# Intercom.net
KiCad netlist of a schematic drawn in EAGLE
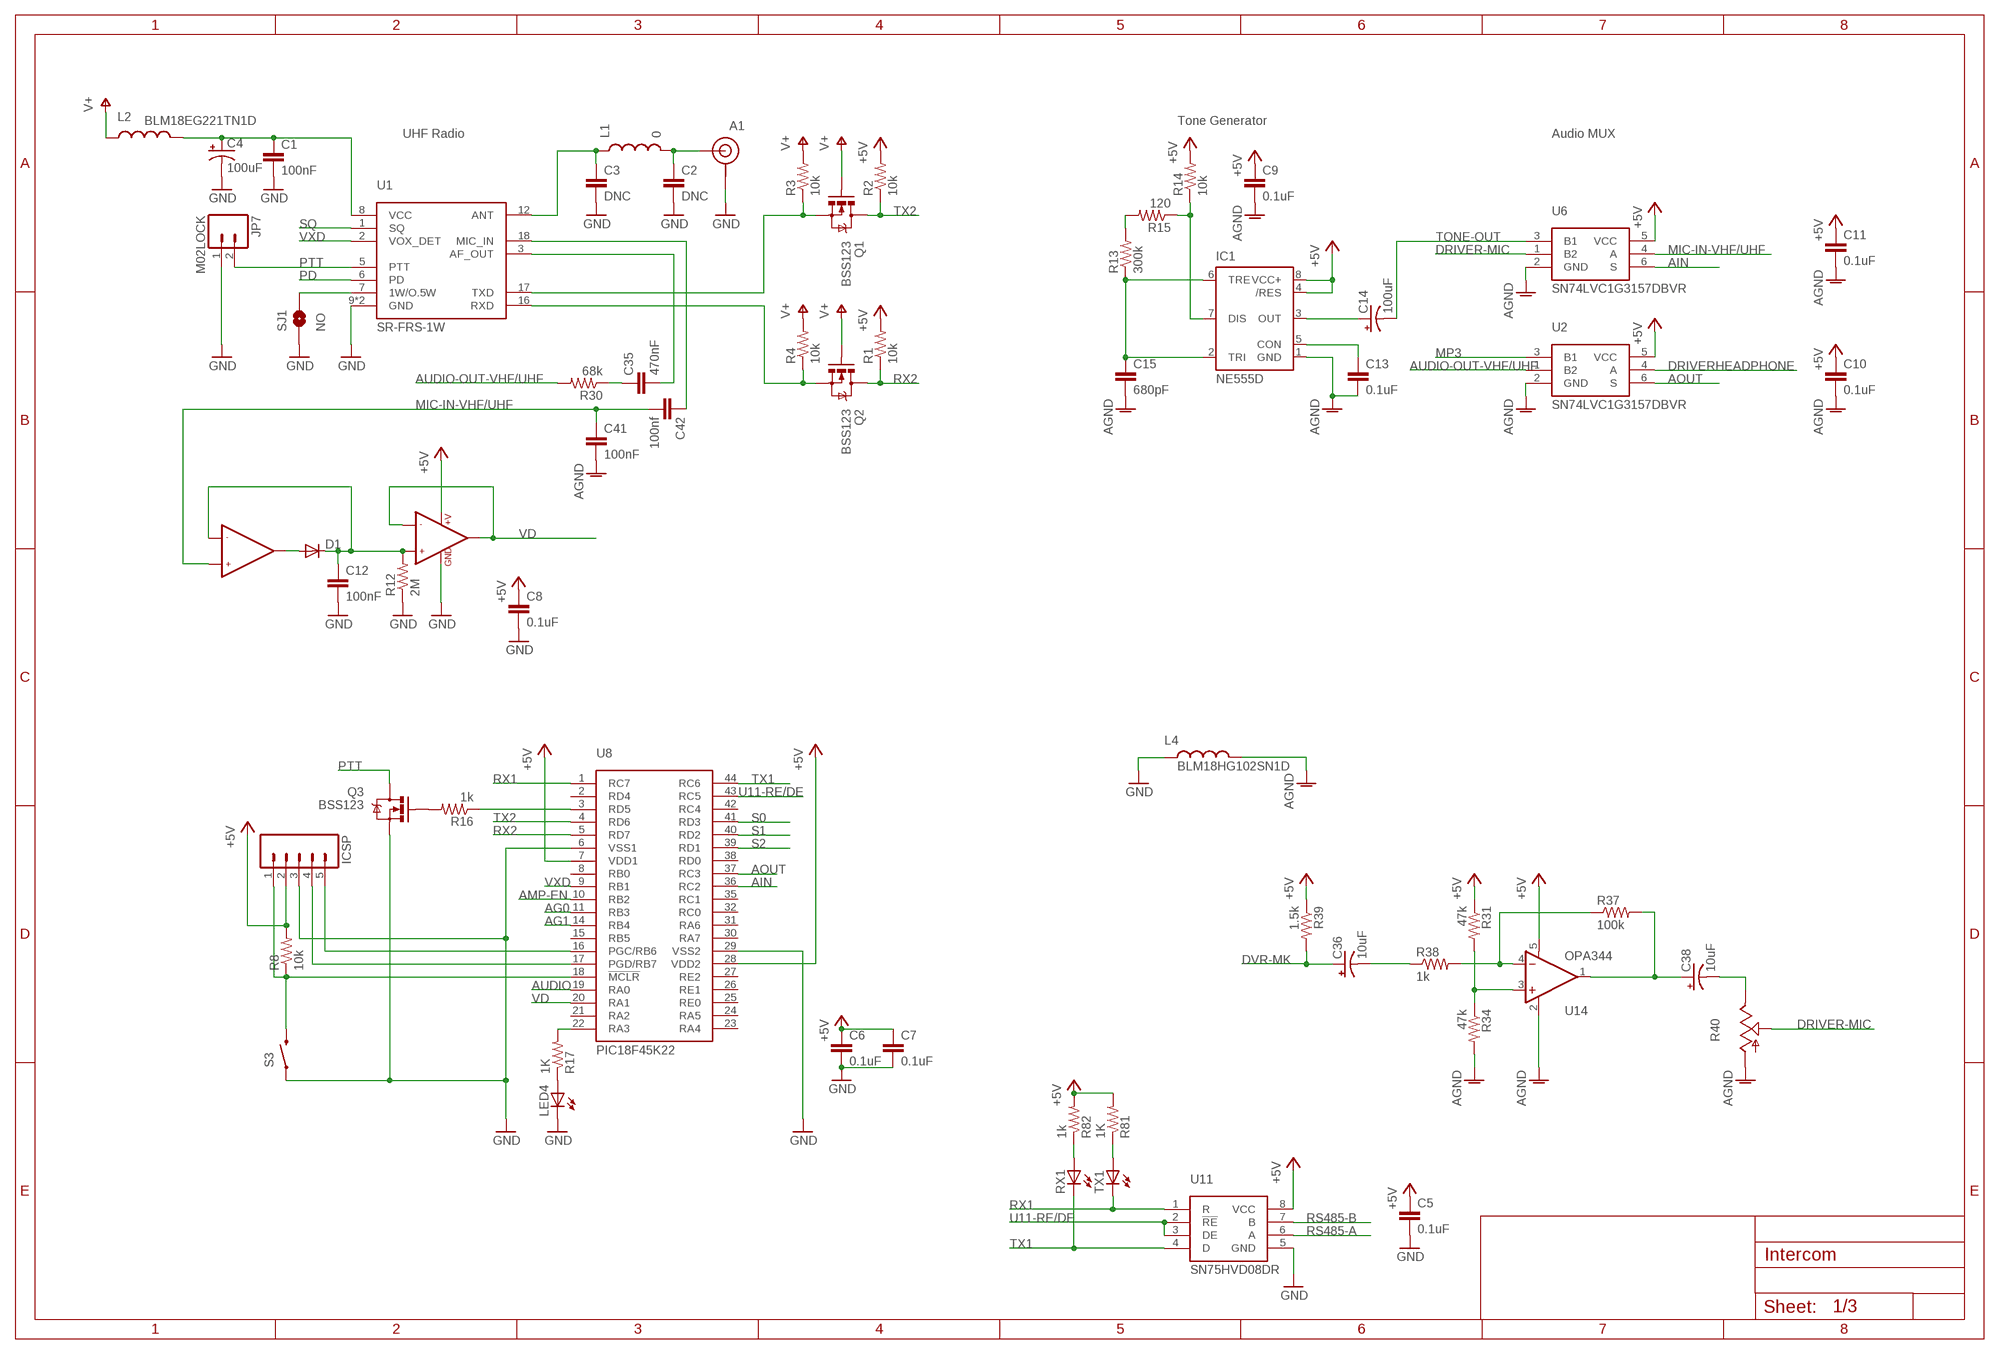
[diagram p0: schematic, sheet 1]
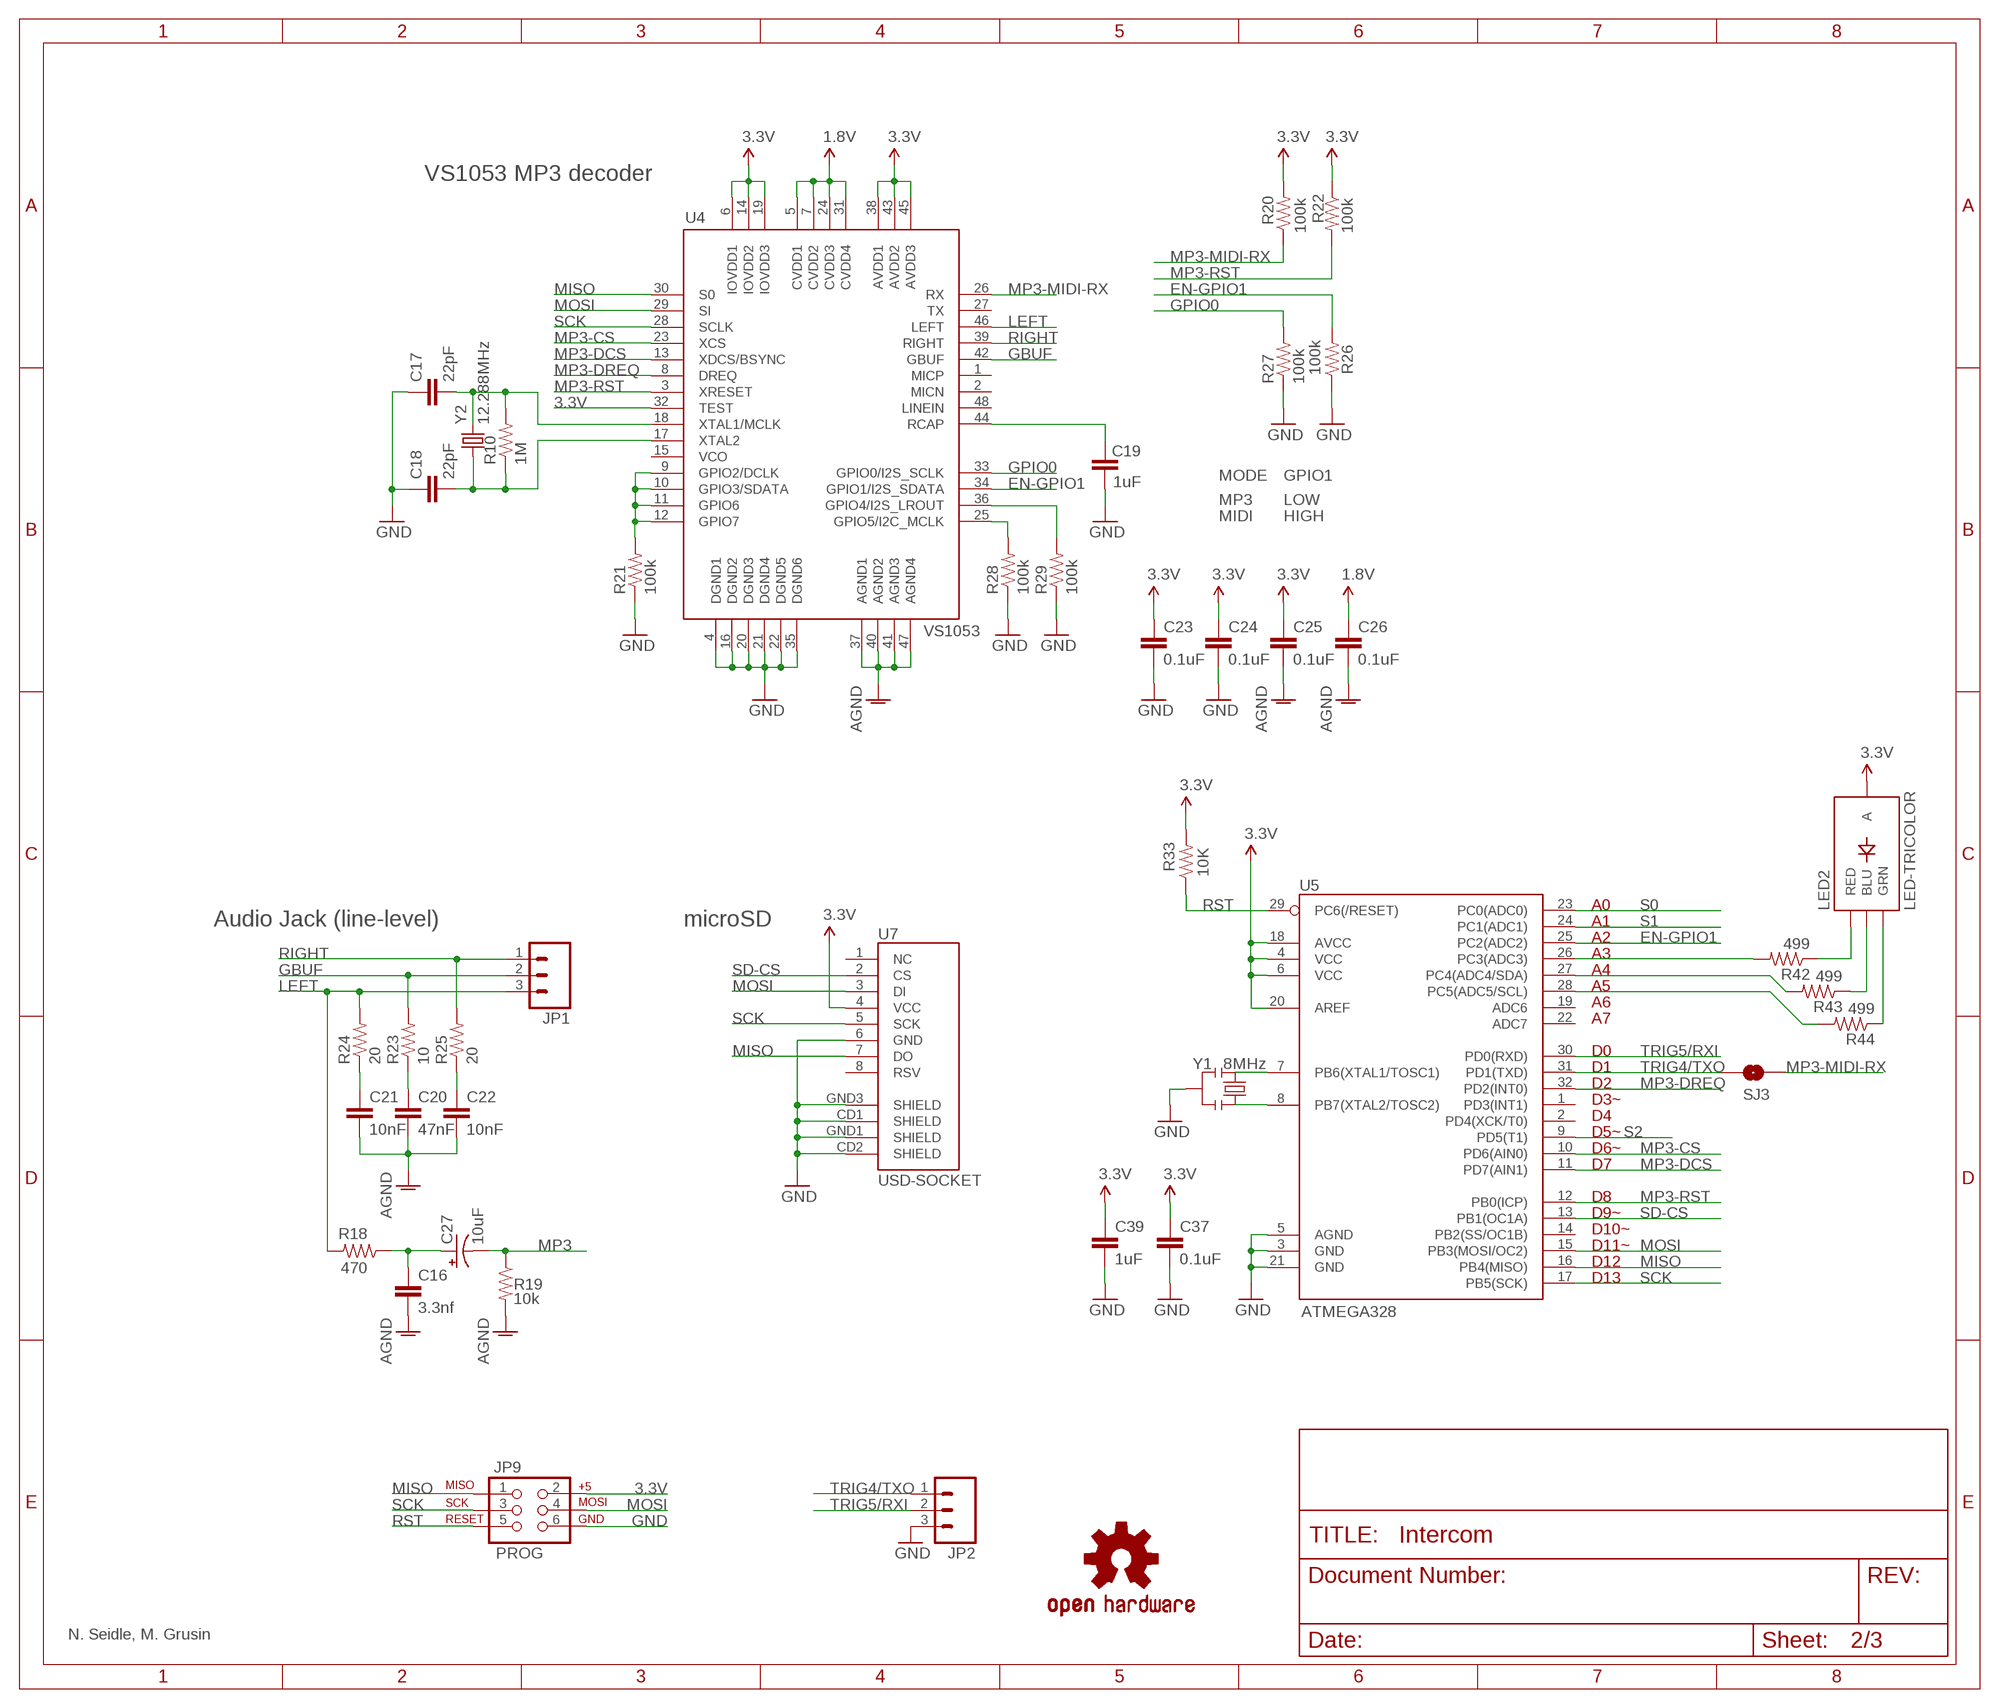
[diagram p1: schematic, sheet 2]
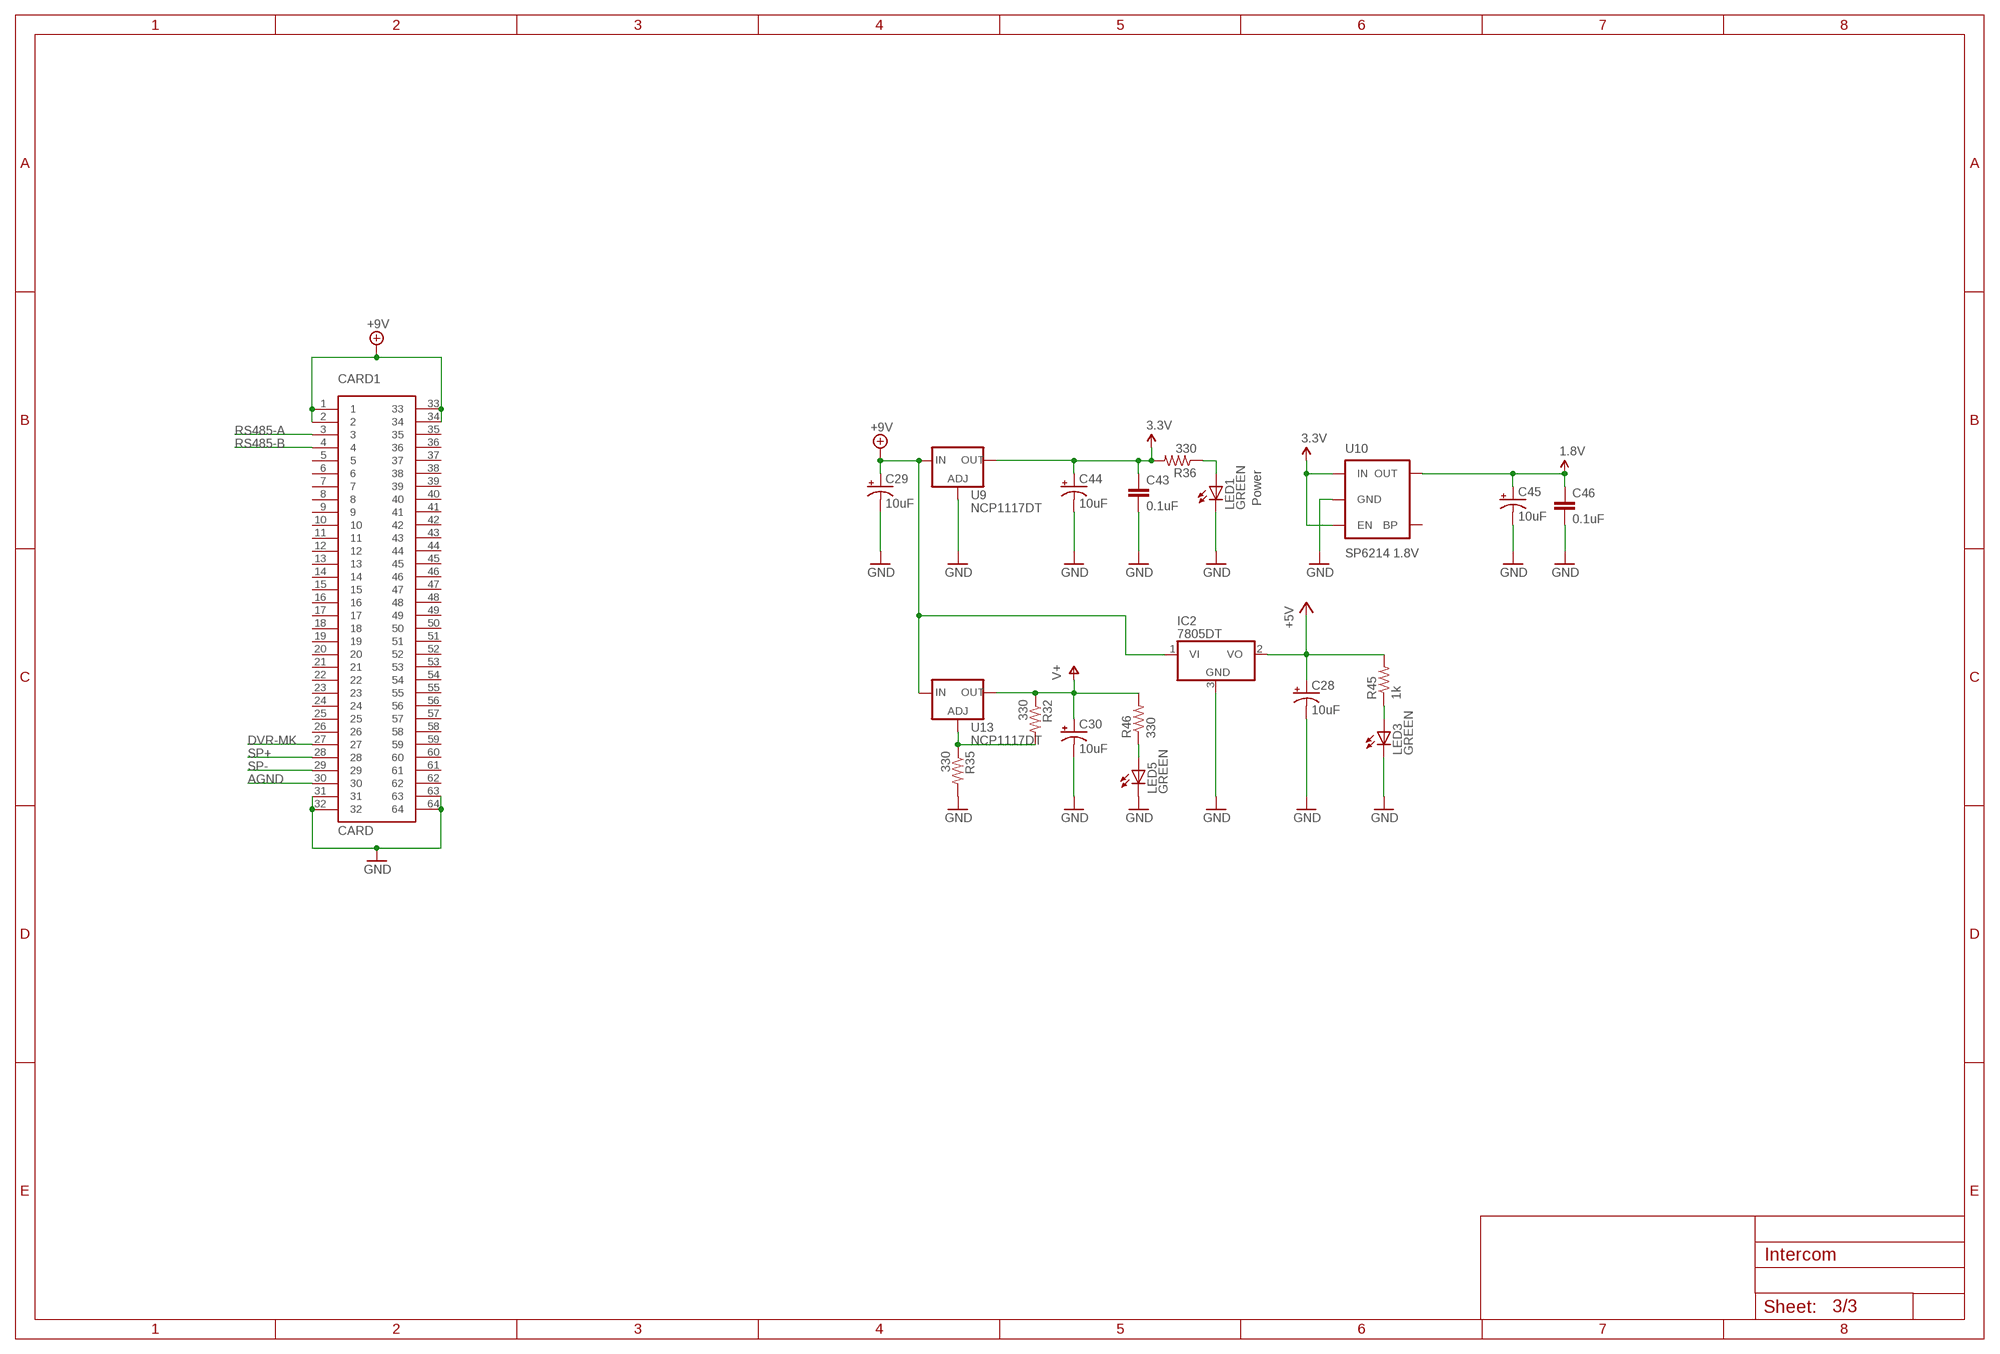
[diagram p2: schematic, sheet 3]

(export (version "E")
  (design (tool "Eeschema 10.0.6"))
  (components
    (comp (ref "C16")
      (value "3.3nf")
      (footprint "eagle-import:0805")
      (libsource (lib "eagle-import") (part "CAP0805"))
    )
    (comp (ref "C17")
      (value "22pF")
      (footprint "eagle-import:0805")
      (libsource (lib "eagle-import") (part "CAP0805"))
    )
    (comp (ref "C18")
      (value "22pF")
      (footprint "eagle-import:0805")
      (libsource (lib "eagle-import") (part "CAP0805"))
    )
    (comp (ref "C19")
      (value "1uF")
      (footprint "eagle-import:0805")
      (libsource (lib "eagle-import") (part "CAP0805"))
    )
    (comp (ref "C20")
      (value "47nF")
      (footprint "eagle-import:0805")
      (libsource (lib "eagle-import") (part "CAP0805"))
    )
    (comp (ref "C21")
      (value "10nF")
      (footprint "eagle-import:0805")
      (libsource (lib "eagle-import") (part "CAP0805"))
    )
    (comp (ref "C22")
      (value "10nF")
      (footprint "eagle-import:0805")
      (libsource (lib "eagle-import") (part "CAP0805"))
    )
    (comp (ref "C23")
      (value "0.1uF")
      (footprint "eagle-import:0805")
      (libsource (lib "eagle-import") (part "CAP0805"))
    )
    (comp (ref "C24")
      (value "0.1uF")
      (footprint "eagle-import:0805")
      (libsource (lib "eagle-import") (part "CAP0805"))
    )
    (comp (ref "C25")
      (value "0.1uF")
      (footprint "eagle-import:0805")
      (libsource (lib "eagle-import") (part "CAP0805"))
    )
    (comp (ref "C26")
      (value "0.1uF")
      (footprint "eagle-import:0805")
      (libsource (lib "eagle-import") (part "CAP0805"))
    )
    (comp (ref "C27")
      (value "10uF")
      (footprint "eagle-import:CT6032")
      (libsource (lib "eagle-import") (part "CPOL-USCT6032"))
    )
    (comp (ref "C37")
      (value "0.1uF")
      (footprint "eagle-import:0805")
      (libsource (lib "eagle-import") (part "CAP0805"))
    )
    (comp (ref "C39")
      (value "1uF")
      (footprint "eagle-import:0805")
      (libsource (lib "eagle-import") (part "CAP0805"))
    )
    (comp (ref "JP1")
      (value "M03PTH")
      (footprint "eagle-import:1X03")
      (libsource (lib "eagle-import") (part "M03PTH"))
    )
    (comp (ref "JP2")
      (value "M03LOCK_LONGPADS")
      (footprint "eagle-import:1X03_LOCK_LONGPADS")
      (libsource (lib "eagle-import") (part "M03LOCK_LONGPADS"))
    )
    (comp (ref "JP9")
      (value "PROG")
      (footprint "eagle-import:2X3-NS")
      (libsource (lib "eagle-import") (part "AVR_SPI_PRG_6NS"))
    )
    (comp (ref "LED2")
      (value "LED-TRICOLOR")
      (footprint "eagle-import:LED-TRICOLOR-SMD")
      (libsource (lib "eagle-import") (part "LED-TRICOLOR"))
    )
    (comp (ref "R10")
      (value "1M")
      (footprint "eagle-import:0805")
      (libsource (lib "eagle-import") (part "RESISTOR0805-RES"))
    )
    (comp (ref "R18")
      (value "470")
      (footprint "eagle-import:0805")
      (libsource (lib "eagle-import") (part "RESISTOR0805-RES"))
    )
    (comp (ref "R19")
      (value "10k")
      (footprint "eagle-import:0805")
      (libsource (lib "eagle-import") (part "RESISTOR0805-RES"))
    )
    (comp (ref "R20")
      (value "100k")
      (footprint "eagle-import:0805")
      (libsource (lib "eagle-import") (part "RESISTOR0805-RES"))
    )
    (comp (ref "R21")
      (value "100k")
      (footprint "eagle-import:0805")
      (libsource (lib "eagle-import") (part "RESISTOR0805-RES"))
    )
    (comp (ref "R22")
      (value "100k")
      (footprint "eagle-import:0805")
      (libsource (lib "eagle-import") (part "RESISTOR0805-RES"))
    )
    (comp (ref "R23")
      (value "10")
      (footprint "eagle-import:0805")
      (libsource (lib "eagle-import") (part "RESISTOR0805-RES"))
    )
    (comp (ref "R24")
      (value "20")
      (footprint "eagle-import:0805")
      (libsource (lib "eagle-import") (part "RESISTOR0805-RES"))
    )
    (comp (ref "R25")
      (value "20")
      (footprint "eagle-import:0805")
      (libsource (lib "eagle-import") (part "RESISTOR0805-RES"))
    )
    (comp (ref "R26")
      (value "100k")
      (footprint "eagle-import:0805")
      (libsource (lib "eagle-import") (part "RESISTOR0805-RES"))
    )
    (comp (ref "R27")
      (value "100k")
      (footprint "eagle-import:0805")
      (libsource (lib "eagle-import") (part "RESISTOR0805-RES"))
    )
    (comp (ref "R28")
      (value "100k")
      (footprint "eagle-import:0805")
      (libsource (lib "eagle-import") (part "RESISTOR0805-RES"))
    )
    (comp (ref "R29")
      (value "100k")
      (footprint "eagle-import:0805")
      (libsource (lib "eagle-import") (part "RESISTOR0805-RES"))
    )
    (comp (ref "R33")
      (value "10K")
      (footprint "eagle-import:0805")
      (libsource (lib "eagle-import") (part "RESISTOR0805-RES"))
    )
    (comp (ref "R42")
      (value "499")
      (footprint "eagle-import:0805")
      (libsource (lib "eagle-import") (part "RESISTOR0805-RES"))
    )
    (comp (ref "R43")
      (value "499")
      (footprint "eagle-import:0805")
      (libsource (lib "eagle-import") (part "RESISTOR0805-RES"))
    )
    (comp (ref "R44")
      (value "499")
      (footprint "eagle-import:0805")
      (libsource (lib "eagle-import") (part "RESISTOR0805-RES"))
    )
    (comp (ref "SJ3")
      (value "SOLDERJUMPERNO")
      (footprint "eagle-import:SJ_2S-NO")
      (libsource (lib "eagle-import") (part "SOLDERJUMPERNO"))
    )
    (comp (ref "U$5")
      (value "OSHW-LOGOM")
      (footprint "eagle-import:OSHW-LOGO-M")
      (libsource (lib "eagle-import") (part "OSHW-LOGOM"))
    )
    (comp (ref "U4")
      (value "VS1053")
      (footprint "eagle-import:LQFP-48")
      (libsource (lib "eagle-import") (part "VS1033"))
    )
    (comp (ref "U5")
      (value "ATMEGA328")
      (footprint "eagle-import:TQFP32-08")
      (libsource (lib "eagle-import") (part "ATMEGA168"))
    )
    (comp (ref "U7")
      (value "USD-SOCKET")
      (footprint "eagle-import:MICRO-SD-SOCKET-PP")
      (libsource (lib "eagle-import") (part "USD-SOCKETNEW"))
    )
    (comp (ref "Y1")
      (value "8MHz")
      (footprint "eagle-import:RESONATOR-SMD")
      (libsource (lib "eagle-import") (part "RESONATORSMD"))
    )
    (comp (ref "Y2")
      (value "12.288MHz")
      (footprint "eagle-import:CRYSTAL-SMD-5X3")
      (libsource (lib "eagle-import") (part "CRYSTAL5X3"))
    )
    (comp (ref "C28")
      (value "10uF")
      (footprint "eagle-import:EIA3216")
      (libsource (lib "eagle-import") (part "CAP_POL1206"))
    )
    (comp (ref "C29")
      (value "10uF")
      (footprint "eagle-import:EIA7343")
      (libsource (lib "eagle-import") (part "CAP_POL7343"))
    )
    (comp (ref "C30")
      (value "10uF")
      (footprint "eagle-import:EIA3216")
      (libsource (lib "eagle-import") (part "CAP_POL1206"))
    )
    (comp (ref "C43")
      (value "0.1uF")
      (footprint "eagle-import:0805")
      (libsource (lib "eagle-import") (part "CAP0805"))
    )
    (comp (ref "C44")
      (value "10uF")
      (footprint "eagle-import:EIA3216")
      (libsource (lib "eagle-import") (part "CAP_POL1206"))
    )
    (comp (ref "C45")
      (value "10uF")
      (footprint "eagle-import:EIA3216")
      (libsource (lib "eagle-import") (part "CAP_POL1206"))
    )
    (comp (ref "C46")
      (value "0.1uF")
      (footprint "eagle-import:0805")
      (libsource (lib "eagle-import") (part "CAP0805"))
    )
    (comp (ref "CARD1")
      (value "CARD")
      (footprint "eagle-import:CARD-64")
      (libsource (lib "eagle-import") (part "CARD"))
    )
    (comp (ref "IC2")
      (value "7805DT")
      (footprint "eagle-import:TO252")
      (libsource (lib "eagle-import") (part "78DT05"))
    )
    (comp (ref "LED1")
      (value "GREEN")
      (footprint "eagle-import:CHIPLED_0805")
      (libsource (lib "eagle-import") (part "LEDCHIPLED_0805"))
    )
    (comp (ref "LED3")
      (value "GREEN")
      (footprint "eagle-import:CHIPLED_0805")
      (libsource (lib "eagle-import") (part "LEDCHIPLED_0805"))
    )
    (comp (ref "LED5")
      (value "GREEN")
      (footprint "eagle-import:CHIPLED_0805")
      (libsource (lib "eagle-import") (part "LEDCHIPLED_0805"))
    )
    (comp (ref "R32")
      (value "330")
      (footprint "eagle-import:0805")
      (libsource (lib "eagle-import") (part "RESISTOR0805-RES"))
    )
    (comp (ref "R35")
      (value "330")
      (footprint "eagle-import:0805")
      (libsource (lib "eagle-import") (part "RESISTOR0805-RES"))
    )
    (comp (ref "R36")
      (value "330")
      (footprint "eagle-import:0805")
      (libsource (lib "eagle-import") (part "RESISTOR0805-RES"))
    )
    (comp (ref "R45")
      (value "1k")
      (footprint "eagle-import:0805")
      (libsource (lib "eagle-import") (part "RESISTOR0805-RES"))
    )
    (comp (ref "R46")
      (value "330")
      (footprint "eagle-import:0805")
      (libsource (lib "eagle-import") (part "RESISTOR0805-RES"))
    )
    (comp (ref "U9")
      (value "NCP1117DT")
      (footprint "eagle-import:V-REG_DPACK")
      (libsource (lib "eagle-import") (part "V_REG_317DPACK"))
    )
    (comp (ref "U10")
      (value "SP6214 1.8V")
      (footprint "eagle-import:SC70")
      (libsource (lib "eagle-import") (part "V_REG_LDOSMD2"))
    )
    (comp (ref "U13")
      (value "NCP1117DT")
      (footprint "eagle-import:V-REG_DPACK")
      (libsource (lib "eagle-import") (part "V_REG_317DPACK"))
    )
    (comp (ref "A1")
      (value "CONSMA003.062")
      (footprint "eagle-import:CONSMA003.062")
      (libsource (lib "eagle-import") (part "CONSMA003.062"))
    )
    (comp (ref "C1")
      (value "100nF")
      (footprint "eagle-import:0805")
      (libsource (lib "eagle-import") (part "SparkFun-Passives_CAP0805"))
    )
    (comp (ref "C2")
      (value "DNC")
      (footprint "eagle-import:0805")
      (libsource (lib "eagle-import") (part "SparkFun-Passives_CAP0805"))
    )
    (comp (ref "C3")
      (value "DNC")
      (footprint "eagle-import:0805")
      (libsource (lib "eagle-import") (part "SparkFun-Passives_CAP0805"))
    )
    (comp (ref "C4")
      (value "100uF")
      (footprint "eagle-import:EIA3216")
      (libsource (lib "eagle-import") (part "SparkFun-Passives_CAP_POL1206"))
    )
    (comp (ref "C5")
      (value "0.1uF")
      (footprint "eagle-import:0805")
      (libsource (lib "eagle-import") (part "SparkFun-Passives_CAP0805"))
    )
    (comp (ref "C6")
      (value "0.1uF")
      (footprint "eagle-import:0805")
      (libsource (lib "eagle-import") (part "SparkFun-Passives_CAP0805"))
    )
    (comp (ref "C7")
      (value "0.1uF")
      (footprint "eagle-import:0805")
      (libsource (lib "eagle-import") (part "SparkFun-Passives_CAP0805"))
    )
    (comp (ref "C8")
      (value "0.1uF")
      (footprint "eagle-import:0805")
      (libsource (lib "eagle-import") (part "SparkFun-Passives_CAP0805"))
    )
    (comp (ref "C9")
      (value "0.1uF")
      (footprint "eagle-import:0805")
      (libsource (lib "eagle-import") (part "SparkFun-Passives_CAP0805"))
    )
    (comp (ref "C10")
      (value "0.1uF")
      (footprint "eagle-import:0805")
      (libsource (lib "eagle-import") (part "SparkFun-Passives_CAP0805"))
    )
    (comp (ref "C11")
      (value "0.1uF")
      (footprint "eagle-import:0805")
      (libsource (lib "eagle-import") (part "SparkFun-Passives_CAP0805"))
    )
    (comp (ref "C12")
      (value "100nF")
      (footprint "eagle-import:0805")
      (libsource (lib "eagle-import") (part "SparkFun-Passives_CAP0805"))
    )
    (comp (ref "C13")
      (value "0.1uF")
      (footprint "eagle-import:0805")
      (libsource (lib "eagle-import") (part "SparkFun-Passives_CAP0805"))
    )
    (comp (ref "C14")
      (value "100uF")
      (footprint "eagle-import:EIA3528-KIT")
      (libsource (lib "eagle-import") (part "SparkFun-Passives_CAP_POL3528-KIT"))
    )
    (comp (ref "C15")
      (value "680pF")
      (footprint "eagle-import:0805")
      (libsource (lib "eagle-import") (part "SparkFun-Passives_CAP0805"))
    )
    (comp (ref "C35")
      (value "470nF")
      (footprint "eagle-import:0805")
      (libsource (lib "eagle-import") (part "SparkFun-Passives_CAP0805"))
    )
    (comp (ref "C36")
      (value "10uF")
      (footprint "eagle-import:EIA3216")
      (libsource (lib "eagle-import") (part "SparkFun-Passives_CAP_POL1206"))
    )
    (comp (ref "C38")
      (value "10uF")
      (footprint "eagle-import:EIA3216")
      (libsource (lib "eagle-import") (part "SparkFun-Passives_CAP_POL1206"))
    )
    (comp (ref "C41")
      (value "100nF")
      (footprint "eagle-import:0805")
      (libsource (lib "eagle-import") (part "SparkFun-Passives_CAP0805"))
    )
    (comp (ref "C42")
      (value "100nf")
      (footprint "eagle-import:0805")
      (libsource (lib "eagle-import") (part "SparkFun-Passives_CAP0805"))
    )
    (comp (ref "D1")
      (value "DIODESOD")
      (footprint "eagle-import:SOD-323")
      (libsource (lib "eagle-import") (part "DIODESOD"))
    )
    (comp (ref "IC1")
      (value "NE555D")
      (footprint "eagle-import:SO08")
      (libsource (lib "eagle-import") (part "NE555D"))
    )
    (comp (ref "ICSP")
      (value "M05LOCK_LONGPADS")
      (footprint "eagle-import:1X05_LOCK_LONGPADS")
      (libsource (lib "eagle-import") (part "M05LOCK_LONGPADS"))
    )
    (comp (ref "JP7")
      (value "M02LOCK")
      (footprint "eagle-import:1X02_LOCK")
      (libsource (lib "eagle-import") (part "M02LOCK"))
    )
    (comp (ref "L1")
      (value "0")
      (footprint "eagle-import:1007")
      (libsource (lib "eagle-import") (part "INDUCTOR1007"))
    )
    (comp (ref "L2")
      (value "BLM18EG221TN1D")
      (footprint "eagle-import:0603")
      (libsource (lib "eagle-import") (part "INDUCTOR0603"))
    )
    (comp (ref "L4")
      (value "BLM18HG102SN1D")
      (footprint "eagle-import:0805")
      (libsource (lib "eagle-import") (part "INDUCTOR0805"))
    )
    (comp (ref "LED4")
      (value "LEDCHIPLED_0805")
      (footprint "eagle-import:CHIPLED_0805")
      (libsource (lib "eagle-import") (part "LEDCHIPLED_0805"))
    )
    (comp (ref "Q1")
      (value "BSS123")
      (footprint "eagle-import:SOT23")
      (libsource (lib "eagle-import") (part "MOSFET-NCHANNELBSS123LT1G"))
    )
    (comp (ref "Q2")
      (value "BSS123")
      (footprint "eagle-import:SOT23")
      (libsource (lib "eagle-import") (part "MOSFET-NCHANNELBSS123LT1G"))
    )
    (comp (ref "Q3")
      (value "BSS123")
      (footprint "eagle-import:SOT23")
      (libsource (lib "eagle-import") (part "MOSFET-NCHANNELBSS123LT1G"))
    )
    (comp (ref "R1")
      (value "10k")
      (footprint "eagle-import:0805")
      (libsource (lib "eagle-import") (part "SparkFun-Passives_RESISTOR0805-RES"))
    )
    (comp (ref "R2")
      (value "10k")
      (footprint "eagle-import:0805")
      (libsource (lib "eagle-import") (part "SparkFun-Passives_RESISTOR0805-RES"))
    )
    (comp (ref "R3")
      (value "10k")
      (footprint "eagle-import:0805")
      (libsource (lib "eagle-import") (part "SparkFun-Passives_RESISTOR0805-RES"))
    )
    (comp (ref "R4")
      (value "10k")
      (footprint "eagle-import:0805")
      (libsource (lib "eagle-import") (part "SparkFun-Passives_RESISTOR0805-RES"))
    )
    (comp (ref "R8")
      (value "10k")
      (footprint "eagle-import:0805")
      (libsource (lib "eagle-import") (part "SparkFun-Passives_RESISTOR0805-RES"))
    )
    (comp (ref "R12")
      (value "2M")
      (footprint "eagle-import:0805")
      (libsource (lib "eagle-import") (part "SparkFun-Passives_RESISTOR0805-RES"))
    )
    (comp (ref "R13")
      (value "300k")
      (footprint "eagle-import:0805")
      (libsource (lib "eagle-import") (part "SparkFun-Passives_RESISTOR0805-RES"))
    )
    (comp (ref "R14")
      (value "10k")
      (footprint "eagle-import:0805")
      (libsource (lib "eagle-import") (part "SparkFun-Passives_RESISTOR0805-RES"))
    )
    (comp (ref "R15")
      (value "120")
      (footprint "eagle-import:0805")
      (libsource (lib "eagle-import") (part "SparkFun-Passives_RESISTOR0805-RES"))
    )
    (comp (ref "R16")
      (value "1k")
      (footprint "eagle-import:0805")
      (libsource (lib "eagle-import") (part "SparkFun-Passives_RESISTOR0805-RES"))
    )
    (comp (ref "R17")
      (value "1K")
      (footprint "eagle-import:R0805")
      (libsource (lib "eagle-import") (part "R-US_R0805"))
    )
    (comp (ref "R30")
      (value "68k")
      (footprint "eagle-import:0805")
      (libsource (lib "eagle-import") (part "SparkFun-Passives_RESISTOR0805-RES"))
    )
    (comp (ref "R31")
      (value "47k")
      (footprint "eagle-import:0805")
      (libsource (lib "eagle-import") (part "SparkFun-Passives_RESISTOR0805-RES"))
    )
    (comp (ref "R34")
      (value "47k")
      (footprint "eagle-import:0805")
      (libsource (lib "eagle-import") (part "SparkFun-Passives_RESISTOR0805-RES"))
    )
    (comp (ref "R37")
      (value "100k")
      (footprint "eagle-import:0805")
      (libsource (lib "eagle-import") (part "SparkFun-Passives_RESISTOR0805-RES"))
    )
    (comp (ref "R38")
      (value "1k")
      (footprint "eagle-import:0805")
      (libsource (lib "eagle-import") (part "SparkFun-Passives_RESISTOR0805-RES"))
    )
    (comp (ref "R39")
      (value "1.5k")
      (footprint "eagle-import:0805")
      (libsource (lib "eagle-import") (part "SparkFun-Passives_RESISTOR0805-RES"))
    )
    (comp (ref "R40")
      (value "TRIM_US-CA6H")
      (footprint "eagle-import:CA6H")
      (libsource (lib "eagle-import") (part "TRIM_US-CA6H"))
    )
    (comp (ref "R81")
      (value "1K")
      (footprint "eagle-import:R0805")
      (libsource (lib "eagle-import") (part "R-US_R0805"))
    )
    (comp (ref "R82")
      (value "1k")
      (footprint "eagle-import:R0805")
      (libsource (lib "eagle-import") (part "R-US_R0805"))
    )
    (comp (ref "RX1")
      (value "LEDCHIPLED_0805")
      (footprint "eagle-import:CHIPLED_0805")
      (libsource (lib "eagle-import") (part "LEDCHIPLED_0805"))
    )
    (comp (ref "S3")
      (value "SWITCH-MOMENTARY-2SIDE_EZ")
      (footprint "eagle-import:TACTILE-PTH-SIDEEZ")
      (libsource (lib "eagle-import") (part "SWITCH-MOMENTARY-2SIDE_EZ"))
    )
    (comp (ref "SJ1")
      (value "NO")
      (footprint "eagle-import:SJ_2S-NO")
      (libsource (lib "eagle-import") (part "SparkFun-Passives_SOLDERJUMPERNO"))
    )
    (comp (ref "TX1")
      (value "LEDCHIPLED_0805")
      (footprint "eagle-import:CHIPLED_0805")
      (libsource (lib "eagle-import") (part "LEDCHIPLED_0805"))
    )
    (comp (ref "U1")
      (value "SR-FRS-1W")
      (footprint "eagle-import:SR-FRS-1W")
      (libsource (lib "eagle-import") (part "SR-FRS-1W"))
    )
    (comp (ref "U2")
      (value "SN74LVC1G3157DBVR")
      (footprint "eagle-import:SOT23-6")
      (libsource (lib "eagle-import") (part "SN74LVC1G3157DBVR"))
    )
    (comp (ref "U6")
      (value "SN74LVC1G3157DBVR")
      (footprint "eagle-import:SOT23-6")
      (libsource (lib "eagle-import") (part "SN74LVC1G3157DBVR"))
    )
    (comp (ref "U8")
      (value "PIC18F45K22")
      (footprint "eagle-import:TQFP-44")
      (libsource (lib "eagle-import") (part "PIC18F45K22"))
    )
    (comp (ref "U11")
      (value "SN75HVD08DR")
      (footprint "eagle-import:SO-8")
      (libsource (lib "eagle-import") (part "SN75HVD08DR"))
    )
    (comp (ref "U12")
      (value "LMV358")
      (footprint "eagle-import:SO08")
      (libsource (lib "eagle-import") (part "LMV358"))
    )
    (comp (ref "U14")
      (value "OPA344")
      (footprint "eagle-import:SOT23-5")
      (libsource (lib "eagle-import") (part "OPA344"))
    )
  )
  (nets
    (net (code "1") (name "+5V") (class "Default")
      (node (ref "C10") (pin "1") (pinfunction "1_1") (pintype "passive"))
      (node (ref "C11") (pin "1") (pinfunction "1_1") (pintype "passive"))
      (node (ref "C28") (pin "A") (pinfunction "+_A") (pintype "passive"))
      (node (ref "C5") (pin "1") (pinfunction "1_1") (pintype "passive"))
      (node (ref "C6") (pin "1") (pinfunction "1_1") (pintype "passive"))
      (node (ref "C7") (pin "1") (pinfunction "1_1") (pintype "passive"))
      (node (ref "C8") (pin "1") (pinfunction "1_1") (pintype "passive"))
      (node (ref "C9") (pin "1") (pinfunction "1_1") (pintype "passive"))
      (node (ref "IC1") (pin "4") (pinfunction "/RES_4") (pintype "input"))
      (node (ref "IC1") (pin "8") (pinfunction "VCC+_8") (pintype "power_in"))
      (node (ref "IC2") (pin "2") (pinfunction "VO_2") (pintype "passive"))
      (node (ref "ICSP") (pin "2") (pinfunction "2_2") (pintype "passive"))
      (node (ref "R1") (pin "2") (pinfunction "2_2") (pintype "passive"))
      (node (ref "R14") (pin "2") (pinfunction "2_2") (pintype "passive"))
      (node (ref "R2") (pin "2") (pinfunction "2_2") (pintype "passive"))
      (node (ref "R31") (pin "1") (pinfunction "1_1") (pintype "passive"))
      (node (ref "R39") (pin "1") (pinfunction "1_1") (pintype "passive"))
      (node (ref "R45") (pin "2") (pinfunction "2_2") (pintype "passive"))
      (node (ref "R8") (pin "2") (pinfunction "2_2") (pintype "passive"))
      (node (ref "R81") (pin "2") (pinfunction "2_2") (pintype "passive"))
      (node (ref "R82") (pin "2") (pinfunction "2_2") (pintype "passive"))
      (node (ref "U11") (pin "8") (pinfunction "VCC_8") (pintype "bidirectional"))
      (node (ref "U12") (pin "8") (pinfunction "+V_8") (pintype "power_in"))
      (node (ref "U14") (pin "5") (pinfunction "V+_5") (pintype "power_in"))
      (node (ref "U2") (pin "5") (pinfunction "VCC_5") (pintype "bidirectional"))
      (node (ref "U6") (pin "5") (pinfunction "VCC_5") (pintype "bidirectional"))
      (node (ref "U8") (pin "28") (pinfunction "VDD2_28") (pintype "bidirectional"))
      (node (ref "U8") (pin "7") (pinfunction "VDD1_7") (pintype "bidirectional"))
    )
    (net (code "2") (name "+9V") (class "Default")
      (node (ref "C29") (pin "A") (pinfunction "+_A") (pintype "passive"))
      (node (ref "CARD1") (pin "1") (pinfunction "1_1") (pintype "bidirectional"))
      (node (ref "CARD1") (pin "2") (pinfunction "2_2") (pintype "bidirectional"))
      (node (ref "CARD1") (pin "33") (pinfunction "33_33") (pintype "bidirectional"))
      (node (ref "CARD1") (pin "34") (pinfunction "34_34") (pintype "bidirectional"))
      (node (ref "IC2") (pin "1") (pinfunction "VI_1") (pintype "input"))
      (node (ref "U13") (pin "3") (pinfunction "IN_3") (pintype "input"))
      (node (ref "U9") (pin "3") (pinfunction "IN_3") (pintype "input"))
    )
    (net (code "3") (name "1.8V") (class "Default")
      (node (ref "C26") (pin "1") (pinfunction "1_1") (pintype "passive"))
      (node (ref "C45") (pin "A") (pinfunction "+_A") (pintype "passive"))
      (node (ref "C46") (pin "1") (pinfunction "1_1") (pintype "passive"))
      (node (ref "U10") (pin "5") (pinfunction "OUT_5") (pintype "passive"))
      (node (ref "U4") (pin "24") (pinfunction "CVDD3_24") (pintype "bidirectional"))
      (node (ref "U4") (pin "31") (pinfunction "CVDD4_31") (pintype "bidirectional"))
      (node (ref "U4") (pin "5") (pinfunction "CVDD1_5") (pintype "bidirectional"))
      (node (ref "U4") (pin "7") (pinfunction "CVDD2_7") (pintype "bidirectional"))
    )
    (net (code "4") (name "3.3V") (class "Default")
      (node (ref "C23") (pin "1") (pinfunction "1_1") (pintype "passive"))
      (node (ref "C24") (pin "1") (pinfunction "1_1") (pintype "passive"))
      (node (ref "C25") (pin "1") (pinfunction "1_1") (pintype "passive"))
      (node (ref "C37") (pin "1") (pinfunction "1_1") (pintype "passive"))
      (node (ref "C39") (pin "1") (pinfunction "1_1") (pintype "passive"))
      (node (ref "C43") (pin "1") (pinfunction "1_1") (pintype "passive"))
      (node (ref "C44") (pin "A") (pinfunction "+_A") (pintype "passive"))
      (node (ref "JP9") (pin "2") (pinfunction "2_2") (pintype "passive"))
      (node (ref "LED2") (pin "A") (pinfunction "A_A") (pintype "bidirectional"))
      (node (ref "R20") (pin "2") (pinfunction "2_2") (pintype "passive"))
      (node (ref "R22") (pin "1") (pinfunction "1_1") (pintype "passive"))
      (node (ref "R33") (pin "2") (pinfunction "2_2") (pintype "passive"))
      (node (ref "R36") (pin "2") (pinfunction "2_2") (pintype "passive"))
      (node (ref "U10") (pin "1") (pinfunction "IN_1") (pintype "input"))
      (node (ref "U10") (pin "3") (pinfunction "EN_3") (pintype "input"))
      (node (ref "U4") (pin "14") (pinfunction "IOVDD2_14") (pintype "bidirectional"))
      (node (ref "U4") (pin "19") (pinfunction "IOVDD3_19") (pintype "bidirectional"))
      (node (ref "U4") (pin "32") (pinfunction "TEST_32") (pintype "bidirectional"))
      (node (ref "U4") (pin "38") (pinfunction "AVDD1_38") (pintype "bidirectional"))
      (node (ref "U4") (pin "43") (pinfunction "AVDD2_43") (pintype "bidirectional"))
      (node (ref "U4") (pin "45") (pinfunction "AVDD3_45") (pintype "bidirectional"))
      (node (ref "U4") (pin "6") (pinfunction "IOVDD1_6") (pintype "bidirectional"))
      (node (ref "U5") (pin "18") (pinfunction "AVCC_18") (pintype "bidirectional"))
      (node (ref "U5") (pin "20") (pinfunction "AREF_20") (pintype "bidirectional"))
      (node (ref "U5") (pin "4") (pinfunction "VCC_4") (pintype "bidirectional"))
      (node (ref "U5") (pin "6") (pinfunction "VCC_6") (pintype "bidirectional"))
      (node (ref "U7") (pin "4") (pinfunction "VCC_4") (pintype "bidirectional"))
      (node (ref "U9") (pin "4") (pinfunction "OUT_4") (pintype "output"))
    )
    (net (code "5") (name "AG0") (class "Default")
      (node (ref "U8") (pin "11") (pinfunction "RB3_11") (pintype "bidirectional"))
    )
    (net (code "6") (name "AG1") (class "Default")
      (node (ref "U8") (pin "14") (pinfunction "RB4_14") (pintype "bidirectional"))
    )
    (net (code "7") (name "AGND") (class "Default")
      (node (ref "C10") (pin "2") (pinfunction "2_2") (pintype "passive"))
      (node (ref "C11") (pin "2") (pinfunction "2_2") (pintype "passive"))
      (node (ref "C13") (pin "2") (pinfunction "2_2") (pintype "passive"))
      (node (ref "C15") (pin "2") (pinfunction "2_2") (pintype "passive"))
      (node (ref "C16") (pin "2") (pinfunction "2_2") (pintype "passive"))
      (node (ref "C20") (pin "2") (pinfunction "2_2") (pintype "passive"))
      (node (ref "C21") (pin "2") (pinfunction "2_2") (pintype "passive"))
      (node (ref "C22") (pin "2") (pinfunction "2_2") (pintype "passive"))
      (node (ref "C25") (pin "2") (pinfunction "2_2") (pintype "passive"))
      (node (ref "C26") (pin "2") (pinfunction "2_2") (pintype "passive"))
      (node (ref "C41") (pin "2") (pinfunction "2_2") (pintype "passive"))
      (node (ref "C9") (pin "2") (pinfunction "2_2") (pintype "passive"))
      (node (ref "CARD1") (pin "30") (pinfunction "30_30") (pintype "bidirectional"))
      (node (ref "IC1") (pin "1") (pinfunction "GND_1") (pintype "power_in"))
      (node (ref "L4") (pin "2") (pinfunction "2_2") (pintype "passive"))
      (node (ref "R19") (pin "2") (pinfunction "2_2") (pintype "passive"))
      (node (ref "R34") (pin "2") (pinfunction "2_2") (pintype "passive"))
      (node (ref "R40") (pin "A") (pinfunction "A_A") (pintype "passive"))
      (node (ref "U14") (pin "2") (pinfunction "V-_2") (pintype "power_in"))
      (node (ref "U2") (pin "2") (pinfunction "GND_2") (pintype "bidirectional"))
      (node (ref "U4") (pin "37") (pinfunction "AGND1_37") (pintype "bidirectional"))
      (node (ref "U4") (pin "40") (pinfunction "AGND2_40") (pintype "bidirectional"))
      (node (ref "U4") (pin "41") (pinfunction "AGND3_41") (pintype "bidirectional"))
      (node (ref "U4") (pin "47") (pinfunction "AGND4_47") (pintype "bidirectional"))
      (node (ref "U6") (pin "2") (pinfunction "GND_2") (pintype "bidirectional"))
    )
    (net (code "8") (name "AIN") (class "Default")
      (node (ref "U6") (pin "6") (pinfunction "S_6") (pintype "bidirectional"))
      (node (ref "U8") (pin "36") (pinfunction "RC2_36") (pintype "bidirectional"))
    )
    (net (code "9") (name "AMP-EN") (class "Default")
      (node (ref "U8") (pin "10") (pinfunction "RB2_10") (pintype "bidirectional"))
    )
    (net (code "10") (name "AOUT") (class "Default")
      (node (ref "U2") (pin "6") (pinfunction "S_6") (pintype "bidirectional"))
      (node (ref "U8") (pin "37") (pinfunction "RC3_37") (pintype "bidirectional"))
    )
    (net (code "11") (name "AUDIO") (class "Default")
      (node (ref "U8") (pin "19") (pinfunction "RA0_19") (pintype "bidirectional"))
    )
    (net (code "12") (name "AUDIO-OUT-VHF{slash}UHF") (class "Default")
      (node (ref "R30") (pin "2") (pinfunction "2_2") (pintype "passive"))
      (node (ref "U2") (pin "1") (pinfunction "B2_1") (pintype "bidirectional"))
    )
    (net (code "13") (name "DRIVER-MIC") (class "Default")
      (node (ref "R40") (pin "S") (pinfunction "S_S") (pintype "passive"))
      (node (ref "U6") (pin "1") (pinfunction "B2_1") (pintype "bidirectional"))
    )
    (net (code "14") (name "DRIVERHEADPHONE") (class "Default")
      (node (ref "U2") (pin "4") (pinfunction "A_4") (pintype "bidirectional"))
    )
    (net (code "15") (name "DVR-MK") (class "Default")
      (node (ref "C36") (pin "A") (pinfunction "+_A") (pintype "passive"))
      (node (ref "CARD1") (pin "27") (pinfunction "27_27") (pintype "bidirectional"))
      (node (ref "R39") (pin "2") (pinfunction "2_2") (pintype "passive"))
    )
    (net (code "16") (name "EN-GPIO1") (class "Default")
      (node (ref "R26") (pin "2") (pinfunction "2_2") (pintype "passive"))
      (node (ref "U4") (pin "34") (pinfunction "GPIO1/I2S_SDATA_34") (pintype "bidirectional"))
      (node (ref "U5") (pin "25") (pinfunction "PC2(ADC2)_25") (pintype "bidirectional"))
    )
    (net (code "17") (name "GBUF") (class "Default")
      (node (ref "JP1") (pin "2") (pinfunction "2_2") (pintype "passive"))
      (node (ref "R23") (pin "2") (pinfunction "2_2") (pintype "passive"))
      (node (ref "U4") (pin "42") (pinfunction "GBUF_42") (pintype "bidirectional"))
    )
    (net (code "18") (name "GND") (class "Default")
      (node (ref "A1") (pin "G") (pinfunction "GND_G") (pintype "bidirectional"))
      (node (ref "A1") (pin "G1") (pinfunction "GND_G1") (pintype "bidirectional"))
      (node (ref "A1") (pin "G2") (pinfunction "GND_G2") (pintype "bidirectional"))
      (node (ref "A1") (pin "G3") (pinfunction "GND_G3") (pintype "bidirectional"))
      (node (ref "C1") (pin "2") (pinfunction "2_2") (pintype "passive"))
      (node (ref "C12") (pin "2") (pinfunction "2_2") (pintype "passive"))
      (node (ref "C17") (pin "1") (pinfunction "1_1") (pintype "passive"))
      (node (ref "C18") (pin "1") (pinfunction "1_1") (pintype "passive"))
      (node (ref "C19") (pin "1") (pinfunction "1_1") (pintype "passive"))
      (node (ref "C2") (pin "2") (pinfunction "2_2") (pintype "passive"))
      (node (ref "C23") (pin "2") (pinfunction "2_2") (pintype "passive"))
      (node (ref "C24") (pin "2") (pinfunction "2_2") (pintype "passive"))
      (node (ref "C28") (pin "C") (pinfunction "-_C") (pintype "passive"))
      (node (ref "C29") (pin "C") (pinfunction "-_C") (pintype "passive"))
      (node (ref "C3") (pin "2") (pinfunction "2_2") (pintype "passive"))
      (node (ref "C30") (pin "C") (pinfunction "-_C") (pintype "passive"))
      (node (ref "C37") (pin "2") (pinfunction "2_2") (pintype "passive"))
      (node (ref "C39") (pin "2") (pinfunction "2_2") (pintype "passive"))
      (node (ref "C4") (pin "C") (pinfunction "-_C") (pintype "passive"))
      (node (ref "C43") (pin "2") (pinfunction "2_2") (pintype "passive"))
      (node (ref "C44") (pin "C") (pinfunction "-_C") (pintype "passive"))
      (node (ref "C45") (pin "C") (pinfunction "-_C") (pintype "passive"))
      (node (ref "C46") (pin "2") (pinfunction "2_2") (pintype "passive"))
      (node (ref "C5") (pin "2") (pinfunction "2_2") (pintype "passive"))
      (node (ref "C6") (pin "2") (pinfunction "2_2") (pintype "passive"))
      (node (ref "C7") (pin "2") (pinfunction "2_2") (pintype "passive"))
      (node (ref "C8") (pin "2") (pinfunction "2_2") (pintype "passive"))
      (node (ref "CARD1") (pin "31") (pinfunction "31_31") (pintype "bidirectional"))
      (node (ref "CARD1") (pin "32") (pinfunction "32_32") (pintype "bidirectional"))
      (node (ref "CARD1") (pin "63") (pinfunction "63_63") (pintype "bidirectional"))
      (node (ref "CARD1") (pin "64") (pinfunction "64_64") (pintype "bidirectional"))
      (node (ref "IC2") (pin "3") (pinfunction "GND_3") (pintype "passive"))
      (node (ref "ICSP") (pin "3") (pinfunction "3_3") (pintype "passive"))
      (node (ref "JP2") (pin "3") (pinfunction "3_3") (pintype "passive"))
      (node (ref "JP7") (pin "1") (pinfunction "1_1") (pintype "passive"))
      (node (ref "JP9") (pin "6") (pinfunction "6_6") (pintype "passive"))
      (node (ref "L4") (pin "1") (pinfunction "1_1") (pintype "passive"))
      (node (ref "LED1") (pin "C") (pinfunction "C_C") (pintype "passive"))
      (node (ref "LED3") (pin "C") (pinfunction "C_C") (pintype "passive"))
      (node (ref "LED4") (pin "C") (pinfunction "C_C") (pintype "passive"))
      (node (ref "LED5") (pin "C") (pinfunction "C_C") (pintype "passive"))
      (node (ref "Q3") (pin "2") (pinfunction "S_2") (pintype "passive"))
      (node (ref "R12") (pin "1") (pinfunction "1_1") (pintype "passive"))
      (node (ref "R21") (pin "1") (pinfunction "1_1") (pintype "passive"))
      (node (ref "R26") (pin "1") (pinfunction "1_1") (pintype "passive"))
      (node (ref "R27") (pin "1") (pinfunction "1_1") (pintype "passive"))
      (node (ref "R28") (pin "1") (pinfunction "1_1") (pintype "passive"))
      (node (ref "R29") (pin "1") (pinfunction "1_1") (pintype "passive"))
      (node (ref "R35") (pin "2") (pinfunction "2_2") (pintype "passive"))
      (node (ref "S3") (pin "1") (pinfunction "1_1") (pintype "passive"))
      (node (ref "SJ1") (pin "1") (pinfunction "1_1") (pintype "passive"))
      (node (ref "U1") (pin "10") (pinfunction "GND_10") (pintype "bidirectional"))
      (node (ref "U1") (pin "9") (pinfunction "GND_9") (pintype "bidirectional"))
      (node (ref "U10") (pin "2") (pinfunction "GND_2") (pintype "input"))
      (node (ref "U11") (pin "5") (pinfunction "GND_5") (pintype "bidirectional"))
      (node (ref "U12") (pin "4") (pinfunction "GND_4") (pintype "power_in"))
      (node (ref "U4") (pin "16") (pinfunction "DGND2_16") (pintype "bidirectional"))
      (node (ref "U4") (pin "20") (pinfunction "DGND3_20") (pintype "bidirectional"))
      (node (ref "U4") (pin "21") (pinfunction "DGND4_21") (pintype "bidirectional"))
      (node (ref "U4") (pin "22") (pinfunction "DGND5_22") (pintype "bidirectional"))
      (node (ref "U4") (pin "35") (pinfunction "DGND6_35") (pintype "bidirectional"))
      (node (ref "U4") (pin "4") (pinfunction "DGND1_4") (pintype "bidirectional"))
      (node (ref "U5") (pin "21") (pinfunction "GND_21") (pintype "bidirectional"))
      (node (ref "U5") (pin "3") (pinfunction "GND_3") (pintype "bidirectional"))
      (node (ref "U5") (pin "5") (pinfunction "AGND_5") (pintype "bidirectional"))
      (node (ref "U7") (pin "6") (pinfunction "GND_6") (pintype "bidirectional"))
      (node (ref "U7") (pin "CD1") (pinfunction "SHIELD_CD1") (pintype "bidirectional"))
      (node (ref "U7") (pin "CD2") (pinfunction "SHIELD_CD2") (pintype "bidirectional"))
      (node (ref "U7") (pin "GND1") (pinfunction "SHIELD_GND1") (pintype "bidirectional"))
      (node (ref "U7") (pin "GND3") (pinfunction "SHIELD_GND3") (pintype "bidirectional"))
      (node (ref "U8") (pin "29") (pinfunction "VSS2_29") (pintype "bidirectional"))
      (node (ref "U8") (pin "6") (pinfunction "VSS1_6") (pintype "bidirectional"))
      (node (ref "U9") (pin "1") (pinfunction "ADJ_1") (pintype "input"))
      (node (ref "Y1") (pin "2") (pinfunction "2_2") (pintype "passive"))
    )
    (net (code "19") (name "GPIO0") (class "Default")
      (node (ref "R27") (pin "2") (pinfunction "2_2") (pintype "passive"))
      (node (ref "U4") (pin "33") (pinfunction "GPIO0/I2S_SCLK_33") (pintype "bidirectional"))
    )
    (net (code "20") (name "LEFT") (class "Default")
      (node (ref "JP1") (pin "3") (pinfunction "3_3") (pintype "passive"))
      (node (ref "R18") (pin "2") (pinfunction "2_2") (pintype "passive"))
      (node (ref "R24") (pin "2") (pinfunction "2_2") (pintype "passive"))
      (node (ref "U4") (pin "46") (pinfunction "LEFT_46") (pintype "bidirectional"))
    )
    (net (code "21") (name "MIC-IN-VHF{slash}UHF") (class "Default")
      (node (ref "C41") (pin "1") (pinfunction "1_1") (pintype "passive"))
      (node (ref "C42") (pin "2") (pinfunction "2_2") (pintype "passive"))
      (node (ref "U12") (pin "5") (pinfunction "+IN2_5") (pintype "input"))
      (node (ref "U6") (pin "4") (pinfunction "A_4") (pintype "bidirectional"))
    )
    (net (code "22") (name "MISO") (class "Default")
      (node (ref "JP9") (pin "1") (pinfunction "1_1") (pintype "passive"))
      (node (ref "U4") (pin "30") (pinfunction "S0_30") (pintype "bidirectional"))
      (node (ref "U5") (pin "16") (pinfunction "PB4(MISO)_16") (pintype "bidirectional"))
      (node (ref "U7") (pin "7") (pinfunction "DO_7") (pintype "bidirectional"))
    )
    (net (code "23") (name "MOSI") (class "Default")
      (node (ref "JP9") (pin "4") (pinfunction "4_4") (pintype "passive"))
      (node (ref "U4") (pin "29") (pinfunction "SI_29") (pintype "bidirectional"))
      (node (ref "U5") (pin "15") (pinfunction "PB3(MOSI/OC2)_15") (pintype "bidirectional"))
      (node (ref "U7") (pin "3") (pinfunction "DI_3") (pintype "bidirectional"))
    )
    (net (code "24") (name "MP3") (class "Default")
      (node (ref "C27") (pin "-") (pinfunction "-_-") (pintype "passive"))
      (node (ref "R19") (pin "1") (pinfunction "1_1") (pintype "passive"))
      (node (ref "U2") (pin "3") (pinfunction "B1_3") (pintype "bidirectional"))
    )
    (net (code "25") (name "MP3-CS") (class "Default")
      (node (ref "U4") (pin "23") (pinfunction "XCS_23") (pintype "bidirectional"))
      (node (ref "U5") (pin "10") (pinfunction "PD6(AIN0)_10") (pintype "bidirectional"))
    )
    (net (code "26") (name "MP3-DCS") (class "Default")
      (node (ref "U4") (pin "13") (pinfunction "XDCS/BSYNC_13") (pintype "bidirectional"))
      (node (ref "U5") (pin "11") (pinfunction "PD7(AIN1)_11") (pintype "bidirectional"))
    )
    (net (code "27") (name "MP3-DREQ") (class "Default")
      (node (ref "U4") (pin "8") (pinfunction "DREQ_8") (pintype "bidirectional"))
      (node (ref "U5") (pin "32") (pinfunction "PD2(INT0)_32") (pintype "bidirectional"))
    )
    (net (code "28") (name "MP3-MIDI-RX") (class "Default")
      (node (ref "R20") (pin "1") (pinfunction "1_1") (pintype "passive"))
      (node (ref "SJ3") (pin "1") (pinfunction "1_1") (pintype "passive"))
      (node (ref "U4") (pin "26") (pinfunction "RX_26") (pintype "bidirectional"))
    )
    (net (code "29") (name "MP3-RST") (class "Default")
      (node (ref "R22") (pin "2") (pinfunction "2_2") (pintype "passive"))
      (node (ref "U4") (pin "3") (pinfunction "XRESET_3") (pintype "bidirectional"))
      (node (ref "U5") (pin "12") (pinfunction "PB0(ICP)_12") (pintype "bidirectional"))
    )
    (net (code "30") (name "Net-(A1-SIGNAL)") (class "Default")
      (node (ref "A1") (pin "S") (pinfunction "SIGNAL_S") (pintype "bidirectional"))
      (node (ref "C2") (pin "1") (pinfunction "1_1") (pintype "passive"))
      (node (ref "L1") (pin "2") (pinfunction "2_2") (pintype "passive"))
    )
    (net (code "31") (name "Net-(C4-+)") (class "Default")
      (node (ref "C1") (pin "1") (pinfunction "1_1") (pintype "passive"))
      (node (ref "C4") (pin "A") (pinfunction "+_A") (pintype "passive"))
      (node (ref "L2") (pin "2") (pinfunction "2_2") (pintype "passive"))
      (node (ref "U1") (pin "8") (pinfunction "VCC_8") (pintype "bidirectional"))
    )
    (net (code "32") (name "Net-(C14-+)") (class "Default")
      (node (ref "C14") (pin "A") (pinfunction "+_A") (pintype "passive"))
      (node (ref "IC1") (pin "3") (pinfunction "OUT_3") (pintype "output"))
    )
    (net (code "33") (name "Net-(C16-Pad1)") (class "Default")
      (node (ref "C16") (pin "1") (pinfunction "1_1") (pintype "passive"))
      (node (ref "C27") (pin "+") (pinfunction "+_+") (pintype "passive"))
      (node (ref "R18") (pin "1") (pinfunction "1_1") (pintype "passive"))
    )
    (net (code "34") (name "Net-(C20-Pad1)") (class "Default")
      (node (ref "C20") (pin "1") (pinfunction "1_1") (pintype "passive"))
      (node (ref "R23") (pin "1") (pinfunction "1_1") (pintype "passive"))
    )
    (net (code "35") (name "Net-(C21-Pad1)") (class "Default")
      (node (ref "C21") (pin "1") (pinfunction "1_1") (pintype "passive"))
      (node (ref "R24") (pin "1") (pinfunction "1_1") (pintype "passive"))
    )
    (net (code "36") (name "Net-(C22-Pad1)") (class "Default")
      (node (ref "C22") (pin "1") (pinfunction "1_1") (pintype "passive"))
      (node (ref "R25") (pin "1") (pinfunction "1_1") (pintype "passive"))
    )
    (net (code "37") (name "Net-(C35-Pad1)") (class "Default")
      (node (ref "C35") (pin "1") (pinfunction "1_1") (pintype "passive"))
      (node (ref "R30") (pin "1") (pinfunction "1_1") (pintype "passive"))
    )
    (net (code "38") (name "Net-(C36--)") (class "Default")
      (node (ref "C36") (pin "C") (pinfunction "-_C") (pintype "passive"))
      (node (ref "R38") (pin "1") (pinfunction "1_1") (pintype "passive"))
    )
    (net (code "39") (name "Net-(C38-+)") (class "Default")
      (node (ref "C38") (pin "A") (pinfunction "+_A") (pintype "passive"))
      (node (ref "R37") (pin "2") (pinfunction "2_2") (pintype "passive"))
      (node (ref "U14") (pin "1") (pinfunction "OUT_1") (pintype "output"))
    )
    (net (code "40") (name "Net-(C38--)") (class "Default")
      (node (ref "C38") (pin "C") (pinfunction "-_C") (pintype "passive"))
      (node (ref "R40") (pin "E") (pinfunction "E_E") (pintype "passive"))
    )
    (net (code "41") (name "Net-(D1-A)") (class "Default")
      (node (ref "D1") (pin "2") (pinfunction "A_2") (pintype "passive"))
      (node (ref "U12") (pin "7") (pinfunction "OUT2_7") (pintype "output"))
    )
    (net (code "42") (name "Net-(D1-C)") (class "Default")
      (node (ref "C12") (pin "1") (pinfunction "1_1") (pintype "passive"))
      (node (ref "D1") (pin "1") (pinfunction "C_1") (pintype "passive"))
      (node (ref "R12") (pin "2") (pinfunction "2_2") (pintype "passive"))
      (node (ref "U12") (pin "3") (pinfunction "+IN1_3") (pintype "input"))
      (node (ref "U12") (pin "6") (pinfunction "-IN2_6") (pintype "input"))
    )
    (net (code "43") (name "Net-(IC1-CON)") (class "Default")
      (node (ref "C13") (pin "1") (pinfunction "1_1") (pintype "passive"))
      (node (ref "IC1") (pin "5") (pinfunction "CON_5") (pintype "input"))
    )
    (net (code "44") (name "Net-(IC1-DIS)") (class "Default")
      (node (ref "IC1") (pin "7") (pinfunction "DIS_7") (pintype "input"))
      (node (ref "R14") (pin "1") (pinfunction "1_1") (pintype "passive"))
      (node (ref "R15") (pin "1") (pinfunction "1_1") (pintype "passive"))
    )
    (net (code "45") (name "Net-(IC1-TRE)") (class "Default")
      (node (ref "C15") (pin "1") (pinfunction "1_1") (pintype "passive"))
      (node (ref "IC1") (pin "2") (pinfunction "TRI_2") (pintype "input"))
      (node (ref "IC1") (pin "6") (pinfunction "TRE_6") (pintype "input"))
      (node (ref "R13") (pin "1") (pinfunction "1_1") (pintype "passive"))
    )
    (net (code "46") (name "Net-(LED1-PadA)") (class "Default")
      (node (ref "LED1") (pin "A") (pinfunction "A_A") (pintype "passive"))
      (node (ref "R36") (pin "1") (pinfunction "1_1") (pintype "passive"))
    )
    (net (code "47") (name "Net-(LED2-BLU)") (class "Default")
      (node (ref "LED2") (pin "B") (pinfunction "BLU_B") (pintype "bidirectional"))
      (node (ref "R43") (pin "1") (pinfunction "1_1") (pintype "passive"))
    )
    (net (code "48") (name "Net-(LED2-GRN)") (class "Default")
      (node (ref "LED2") (pin "G") (pinfunction "GRN_G") (pintype "bidirectional"))
      (node (ref "R44") (pin "1") (pinfunction "1_1") (pintype "passive"))
    )
    (net (code "49") (name "Net-(LED2-RED)") (class "Default")
      (node (ref "LED2") (pin "R") (pinfunction "RED_R") (pintype "bidirectional"))
      (node (ref "R42") (pin "1") (pinfunction "1_1") (pintype "passive"))
    )
    (net (code "50") (name "Net-(LED3-PadA)") (class "Default")
      (node (ref "LED3") (pin "A") (pinfunction "A_A") (pintype "passive"))
      (node (ref "R45") (pin "1") (pinfunction "1_1") (pintype "passive"))
    )
    (net (code "51") (name "Net-(LED4-PadA)") (class "Default")
      (node (ref "LED4") (pin "A") (pinfunction "A_A") (pintype "passive"))
      (node (ref "R17") (pin "1") (pinfunction "1_1") (pintype "passive"))
    )
    (net (code "52") (name "Net-(LED5-PadA)") (class "Default")
      (node (ref "LED5") (pin "A") (pinfunction "A_A") (pintype "passive"))
      (node (ref "R46") (pin "1") (pinfunction "1_1") (pintype "passive"))
    )
    (net (code "53") (name "Net-(Q1-S)") (class "Default")
      (node (ref "Q1") (pin "2") (pinfunction "S_2") (pintype "passive"))
      (node (ref "R3") (pin "1") (pinfunction "1_1") (pintype "passive"))
      (node (ref "U1") (pin "17") (pinfunction "TXD_17") (pintype "bidirectional"))
    )
    (net (code "54") (name "Net-(Q2-S)") (class "Default")
      (node (ref "Q2") (pin "2") (pinfunction "S_2") (pintype "passive"))
      (node (ref "R4") (pin "1") (pinfunction "1_1") (pintype "passive"))
      (node (ref "U1") (pin "16") (pinfunction "RXD_16") (pintype "bidirectional"))
    )
    (net (code "55") (name "Net-(Q3-G)") (class "Default")
      (node (ref "Q3") (pin "1") (pinfunction "G_1") (pintype "passive"))
      (node (ref "R16") (pin "2") (pinfunction "2_2") (pintype "passive"))
    )
    (net (code "56") (name "Net-(R13-Pad2)") (class "Default")
      (node (ref "R13") (pin "2") (pinfunction "2_2") (pintype "passive"))
      (node (ref "R15") (pin "2") (pinfunction "2_2") (pintype "passive"))
    )
    (net (code "57") (name "Net-(R81-Pad1)") (class "Default")
      (node (ref "R81") (pin "1") (pinfunction "1_1") (pintype "passive"))
      (node (ref "TX1") (pin "A") (pinfunction "A_A") (pintype "passive"))
    )
    (net (code "58") (name "Net-(R82-Pad1)") (class "Default")
      (node (ref "R82") (pin "1") (pinfunction "1_1") (pintype "passive"))
      (node (ref "RX1") (pin "A") (pinfunction "A_A") (pintype "passive"))
    )
    (net (code "59") (name "Net-(U1-1W{slash}O.5W)") (class "Default")
      (node (ref "SJ1") (pin "2") (pinfunction "2_2") (pintype "passive"))
      (node (ref "U1") (pin "7") (pinfunction "1W/O.5W_7") (pintype "bidirectional"))
    )
    (net (code "60") (name "Net-(U1-AF_OUT)") (class "Default")
      (node (ref "C35") (pin "2") (pinfunction "2_2") (pintype "passive"))
      (node (ref "U1") (pin "3") (pinfunction "AF_OUT_3") (pintype "bidirectional"))
    )
    (net (code "61") (name "Net-(U1-ANT)") (class "Default")
      (node (ref "C3") (pin "1") (pinfunction "1_1") (pintype "passive"))
      (node (ref "L1") (pin "1") (pinfunction "1_1") (pintype "passive"))
      (node (ref "U1") (pin "12") (pinfunction "ANT_12") (pintype "bidirectional"))
    )
    (net (code "62") (name "Net-(U1-MIC_IN)") (class "Default")
      (node (ref "C42") (pin "1") (pinfunction "1_1") (pintype "passive"))
      (node (ref "U1") (pin "18") (pinfunction "MIC_IN_18") (pintype "bidirectional"))
    )
    (net (code "63") (name "Net-(U4-GPIO2{slash}DCLK)") (class "Default")
      (node (ref "R21") (pin "2") (pinfunction "2_2") (pintype "passive"))
      (node (ref "U4") (pin "10") (pinfunction "GPIO3/SDATA_10") (pintype "bidirectional"))
      (node (ref "U4") (pin "11") (pinfunction "GPIO6_11") (pintype "bidirectional"))
      (node (ref "U4") (pin "12") (pinfunction "GPIO7_12") (pintype "bidirectional"))
      (node (ref "U4") (pin "9") (pinfunction "GPIO2/DCLK_9") (pintype "bidirectional"))
    )
    (net (code "64") (name "Net-(U4-GPIO4{slash}I2S_LROUT)") (class "Default")
      (node (ref "R29") (pin "2") (pinfunction "2_2") (pintype "passive"))
      (node (ref "U4") (pin "36") (pinfunction "GPIO4/I2S_LROUT_36") (pintype "bidirectional"))
    )
    (net (code "65") (name "Net-(U4-GPIO5{slash}I2C_MCLK)") (class "Default")
      (node (ref "R28") (pin "2") (pinfunction "2_2") (pintype "passive"))
      (node (ref "U4") (pin "25") (pinfunction "GPIO5/I2C_MCLK_25") (pintype "bidirectional"))
    )
    (net (code "66") (name "Net-(U4-RCAP)") (class "Default")
      (node (ref "C19") (pin "2") (pinfunction "2_2") (pintype "passive"))
      (node (ref "U4") (pin "44") (pinfunction "RCAP_44") (pintype "bidirectional"))
    )
    (net (code "67") (name "Net-(U4-XTAL1{slash}MCLK)") (class "Default")
      (node (ref "C17") (pin "2") (pinfunction "2_2") (pintype "passive"))
      (node (ref "R10") (pin "2") (pinfunction "2_2") (pintype "passive"))
      (node (ref "U4") (pin "18") (pinfunction "XTAL1/MCLK_18") (pintype "bidirectional"))
      (node (ref "Y2") (pin "3") (pinfunction "2_3") (pintype "passive"))
    )
    (net (code "68") (name "Net-(U4-XTAL2)") (class "Default")
      (node (ref "C18") (pin "2") (pinfunction "2_2") (pintype "passive"))
      (node (ref "R10") (pin "1") (pinfunction "1_1") (pintype "passive"))
      (node (ref "U4") (pin "17") (pinfunction "XTAL2_17") (pintype "bidirectional"))
      (node (ref "Y2") (pin "1") (pinfunction "1_1") (pintype "passive"))
    )
    (net (code "69") (name "Net-(U5-PB6(XTAL1{slash}TOSC1))") (class "Default")
      (node (ref "U5") (pin "7") (pinfunction "PB6(XTAL1/TOSC1)_7") (pintype "bidirectional"))
      (node (ref "Y1") (pin "1") (pinfunction "1_1") (pintype "passive"))
    )
    (net (code "70") (name "Net-(U5-PB7(XTAL2{slash}TOSC2))") (class "Default")
      (node (ref "U5") (pin "8") (pinfunction "PB7(XTAL2/TOSC2)_8") (pintype "bidirectional"))
      (node (ref "Y1") (pin "3") (pinfunction "3_3") (pintype "passive"))
    )
    (net (code "71") (name "Net-(U5-PC3(ADC3))") (class "Default")
      (node (ref "R42") (pin "2") (pinfunction "2_2") (pintype "passive"))
      (node (ref "U5") (pin "26") (pinfunction "PC3(ADC3)_26") (pintype "bidirectional"))
    )
    (net (code "72") (name "Net-(U5-PC4(ADC4{slash}SDA))") (class "Default")
      (node (ref "R43") (pin "2") (pinfunction "2_2") (pintype "passive"))
      (node (ref "U5") (pin "27") (pinfunction "PC4(ADC4/SDA)_27") (pintype "bidirectional"))
    )
    (net (code "73") (name "Net-(U5-PC5(ADC5{slash}SCL))") (class "Default")
      (node (ref "R44") (pin "2") (pinfunction "2_2") (pintype "passive"))
      (node (ref "U5") (pin "28") (pinfunction "PC5(ADC5/SCL)_28") (pintype "bidirectional"))
    )
    (net (code "74") (name "Net-(U8-PGC{slash}RB6)") (class "Default")
      (node (ref "ICSP") (pin "5") (pinfunction "5_5") (pintype "passive"))
      (node (ref "U8") (pin "16") (pinfunction "PGC/RB6_16") (pintype "bidirectional"))
    )
    (net (code "75") (name "Net-(U8-PGD{slash}RB7)") (class "Default")
      (node (ref "ICSP") (pin "4") (pinfunction "4_4") (pintype "passive"))
      (node (ref "U8") (pin "17") (pinfunction "PGD/RB7_17") (pintype "bidirectional"))
    )
    (net (code "76") (name "Net-(U8-RA3)") (class "Default")
      (node (ref "R17") (pin "2") (pinfunction "2_2") (pintype "passive"))
      (node (ref "U8") (pin "22") (pinfunction "RA3_22") (pintype "bidirectional"))
    )
    (net (code "77") (name "Net-(U8-RD5)") (class "Default")
      (node (ref "R16") (pin "1") (pinfunction "1_1") (pintype "passive"))
      (node (ref "U8") (pin "3") (pinfunction "RD5_3") (pintype "bidirectional"))
    )
    (net (code "78") (name "Net-(U8-~{MCLR})") (class "Default")
      (node (ref "ICSP") (pin "1") (pinfunction "1_1") (pintype "passive"))
      (node (ref "R8") (pin "1") (pinfunction "1_1") (pintype "passive"))
      (node (ref "S3") (pin "2") (pinfunction "2_2") (pintype "passive"))
      (node (ref "U8") (pin "18") (pinfunction "~{MCLR}_18") (pintype "bidirectional"))
    )
    (net (code "79") (name "Net-(U13-ADJ)") (class "Default")
      (node (ref "R32") (pin "2") (pinfunction "2_2") (pintype "passive"))
      (node (ref "R35") (pin "1") (pinfunction "1_1") (pintype "passive"))
      (node (ref "U13") (pin "1") (pinfunction "ADJ_1") (pintype "input"))
    )
    (net (code "80") (name "Net-(U14-+IN)") (class "Default")
      (node (ref "R31") (pin "2") (pinfunction "2_2") (pintype "passive"))
      (node (ref "R34") (pin "1") (pinfunction "1_1") (pintype "passive"))
      (node (ref "U14") (pin "3") (pinfunction "+IN_3") (pintype "input"))
    )
    (net (code "81") (name "Net-(U14--IN)") (class "Default")
      (node (ref "R37") (pin "1") (pinfunction "1_1") (pintype "passive"))
      (node (ref "R38") (pin "2") (pinfunction "2_2") (pintype "passive"))
      (node (ref "U14") (pin "4") (pinfunction "-IN_4") (pintype "input"))
    )
    (net (code "82") (name "PD") (class "Default")
      (node (ref "U1") (pin "6") (pinfunction "PD_6") (pintype "bidirectional"))
    )
    (net (code "83") (name "PTT") (class "Default")
      (node (ref "JP7") (pin "2") (pinfunction "2_2") (pintype "passive"))
      (node (ref "Q3") (pin "3") (pinfunction "D_3") (pintype "passive"))
      (node (ref "U1") (pin "5") (pinfunction "PTT_5") (pintype "bidirectional"))
    )
    (net (code "84") (name "RIGHT") (class "Default")
      (node (ref "JP1") (pin "1") (pinfunction "1_1") (pintype "passive"))
      (node (ref "R25") (pin "2") (pinfunction "2_2") (pintype "passive"))
      (node (ref "U4") (pin "39") (pinfunction "RIGHT_39") (pintype "bidirectional"))
    )
    (net (code "85") (name "RS485-A") (class "Default")
      (node (ref "CARD1") (pin "3") (pinfunction "3_3") (pintype "bidirectional"))
      (node (ref "U11") (pin "6") (pinfunction "A_6") (pintype "bidirectional"))
    )
    (net (code "86") (name "RS485-B") (class "Default")
      (node (ref "CARD1") (pin "4") (pinfunction "4_4") (pintype "bidirectional"))
      (node (ref "U11") (pin "7") (pinfunction "B_7") (pintype "bidirectional"))
    )
    (net (code "87") (name "RST") (class "Default")
      (node (ref "JP9") (pin "5") (pinfunction "5_5") (pintype "passive"))
      (node (ref "R33") (pin "1") (pinfunction "1_1") (pintype "passive"))
      (node (ref "U5") (pin "29") (pinfunction "PC6(/RESET)_29") (pintype "bidirectional"))
    )
    (net (code "88") (name "RX1") (class "Default")
      (node (ref "TX1") (pin "C") (pinfunction "C_C") (pintype "passive"))
      (node (ref "U11") (pin "1") (pinfunction "R_1") (pintype "bidirectional"))
      (node (ref "U8") (pin "1") (pinfunction "RC7_1") (pintype "bidirectional"))
    )
    (net (code "89") (name "RX2") (class "Default")
      (node (ref "Q2") (pin "3") (pinfunction "D_3") (pintype "passive"))
      (node (ref "R1") (pin "1") (pinfunction "1_1") (pintype "passive"))
      (node (ref "U8") (pin "5") (pinfunction "RD7_5") (pintype "bidirectional"))
    )
    (net (code "90") (name "S0") (class "Default")
      (node (ref "U5") (pin "23") (pinfunction "PC0(ADC0)_23") (pintype "bidirectional"))
      (node (ref "U8") (pin "41") (pinfunction "RD3_41") (pintype "bidirectional"))
    )
    (net (code "91") (name "S1") (class "Default")
      (node (ref "U5") (pin "24") (pinfunction "PC1(ADC1)_24") (pintype "bidirectional"))
      (node (ref "U8") (pin "40") (pinfunction "RD2_40") (pintype "bidirectional"))
    )
    (net (code "92") (name "S2") (class "Default")
      (node (ref "U5") (pin "9") (pinfunction "PD5(T1)_9") (pintype "bidirectional"))
      (node (ref "U8") (pin "39") (pinfunction "RD1_39") (pintype "bidirectional"))
    )
    (net (code "93") (name "SCK") (class "Default")
      (node (ref "JP9") (pin "3") (pinfunction "3_3") (pintype "passive"))
      (node (ref "U4") (pin "28") (pinfunction "SCLK_28") (pintype "bidirectional"))
      (node (ref "U5") (pin "17") (pinfunction "PB5(SCK)_17") (pintype "bidirectional"))
      (node (ref "U7") (pin "5") (pinfunction "SCK_5") (pintype "bidirectional"))
    )
    (net (code "94") (name "SD-CS") (class "Default")
      (node (ref "U5") (pin "13") (pinfunction "PB1(OC1A)_13") (pintype "bidirectional"))
      (node (ref "U7") (pin "2") (pinfunction "CS_2") (pintype "bidirectional"))
    )
    (net (code "95") (name "SP+") (class "Default")
      (node (ref "CARD1") (pin "28") (pinfunction "28_28") (pintype "bidirectional"))
    )
    (net (code "96") (name "SP-") (class "Default")
      (node (ref "CARD1") (pin "29") (pinfunction "29_29") (pintype "bidirectional"))
    )
    (net (code "97") (name "SQ") (class "Default")
      (node (ref "U1") (pin "1") (pinfunction "SQ_1") (pintype "bidirectional"))
    )
    (net (code "98") (name "TONE-OUT") (class "Default")
      (node (ref "C14") (pin "C") (pinfunction "-_C") (pintype "passive"))
      (node (ref "U6") (pin "3") (pinfunction "B1_3") (pintype "bidirectional"))
    )
    (net (code "99") (name "TRIG4{slash}TXO") (class "Default")
      (node (ref "JP2") (pin "1") (pinfunction "1_1") (pintype "passive"))
      (node (ref "SJ3") (pin "2") (pinfunction "2_2") (pintype "passive"))
      (node (ref "U5") (pin "31") (pinfunction "PD1(TXD)_31") (pintype "bidirectional"))
    )
    (net (code "100") (name "TRIG5{slash}RXI") (class "Default")
      (node (ref "JP2") (pin "2") (pinfunction "2_2") (pintype "passive"))
      (node (ref "U5") (pin "30") (pinfunction "PD0(RXD)_30") (pintype "bidirectional"))
    )
    (net (code "101") (name "TX1") (class "Default")
      (node (ref "RX1") (pin "C") (pinfunction "C_C") (pintype "passive"))
      (node (ref "U11") (pin "4") (pinfunction "D_4") (pintype "bidirectional"))
      (node (ref "U8") (pin "44") (pinfunction "RC6_44") (pintype "bidirectional"))
    )
    (net (code "102") (name "TX2") (class "Default")
      (node (ref "Q1") (pin "3") (pinfunction "D_3") (pintype "passive"))
      (node (ref "R2") (pin "1") (pinfunction "1_1") (pintype "passive"))
      (node (ref "U8") (pin "4") (pinfunction "RD6_4") (pintype "bidirectional"))
    )
    (net (code "103") (name "U11-RE{slash}DE") (class "Default")
      (node (ref "U11") (pin "2") (pinfunction "~{RE}_2") (pintype "bidirectional"))
      (node (ref "U11") (pin "3") (pinfunction "DE_3") (pintype "bidirectional"))
      (node (ref "U8") (pin "43") (pinfunction "RC5_43") (pintype "bidirectional"))
    )
    (net (code "104") (name "V+") (class "Default")
      (node (ref "C30") (pin "A") (pinfunction "+_A") (pintype "passive"))
      (node (ref "L2") (pin "1") (pinfunction "1_1") (pintype "passive"))
      (node (ref "Q1") (pin "1") (pinfunction "G_1") (pintype "passive"))
      (node (ref "Q2") (pin "1") (pinfunction "G_1") (pintype "passive"))
      (node (ref "R3") (pin "2") (pinfunction "2_2") (pintype "passive"))
      (node (ref "R32") (pin "1") (pinfunction "1_1") (pintype "passive"))
      (node (ref "R4") (pin "2") (pinfunction "2_2") (pintype "passive"))
      (node (ref "R46") (pin "2") (pinfunction "2_2") (pintype "passive"))
      (node (ref "U13") (pin "4") (pinfunction "OUT_4") (pintype "output"))
    )
    (net (code "105") (name "VD") (class "Default")
      (node (ref "U12") (pin "1") (pinfunction "OUT1_1") (pintype "output"))
      (node (ref "U12") (pin "2") (pinfunction "-IN1_2") (pintype "input"))
      (node (ref "U8") (pin "20") (pinfunction "RA1_20") (pintype "bidirectional"))
    )
    (net (code "106") (name "VXD") (class "Default")
      (node (ref "U1") (pin "2") (pinfunction "VOX_DET_2") (pintype "bidirectional"))
      (node (ref "U8") (pin "9") (pinfunction "RB1_9") (pintype "bidirectional"))
    )
    (net (code "107") (name "unconnected-(CARD1-Pad5)") (class "Default")
      (node (ref "CARD1") (pin "5") (pinfunction "5_5") (pintype "bidirectional"))
    )
    (net (code "108") (name "unconnected-(CARD1-Pad6)") (class "Default")
      (node (ref "CARD1") (pin "6") (pinfunction "6_6") (pintype "bidirectional"))
    )
    (net (code "109") (name "unconnected-(CARD1-Pad7)") (class "Default")
      (node (ref "CARD1") (pin "7") (pinfunction "7_7") (pintype "bidirectional"))
    )
    (net (code "110") (name "unconnected-(CARD1-Pad8)") (class "Default")
      (node (ref "CARD1") (pin "8") (pinfunction "8_8") (pintype "bidirectional"))
    )
    (net (code "111") (name "unconnected-(CARD1-Pad9)") (class "Default")
      (node (ref "CARD1") (pin "9") (pinfunction "9_9") (pintype "bidirectional"))
    )
    (net (code "112") (name "unconnected-(CARD1-Pad10)") (class "Default")
      (node (ref "CARD1") (pin "10") (pinfunction "10_10") (pintype "bidirectional"))
    )
    (net (code "113") (name "unconnected-(CARD1-Pad11)") (class "Default")
      (node (ref "CARD1") (pin "11") (pinfunction "11_11") (pintype "bidirectional"))
    )
    (net (code "114") (name "unconnected-(CARD1-Pad12)") (class "Default")
      (node (ref "CARD1") (pin "12") (pinfunction "12_12") (pintype "bidirectional"))
    )
    (net (code "115") (name "unconnected-(CARD1-Pad13)") (class "Default")
      (node (ref "CARD1") (pin "13") (pinfunction "13_13") (pintype "bidirectional"))
    )
    (net (code "116") (name "unconnected-(CARD1-Pad14)") (class "Default")
      (node (ref "CARD1") (pin "14") (pinfunction "14_14") (pintype "bidirectional"))
    )
    (net (code "117") (name "unconnected-(CARD1-Pad15)") (class "Default")
      (node (ref "CARD1") (pin "15") (pinfunction "15_15") (pintype "bidirectional"))
    )
    (net (code "118") (name "unconnected-(CARD1-Pad16)") (class "Default")
      (node (ref "CARD1") (pin "16") (pinfunction "16_16") (pintype "bidirectional"))
    )
    (net (code "119") (name "unconnected-(CARD1-Pad17)") (class "Default")
      (node (ref "CARD1") (pin "17") (pinfunction "17_17") (pintype "bidirectional"))
    )
    (net (code "120") (name "unconnected-(CARD1-Pad18)") (class "Default")
      (node (ref "CARD1") (pin "18") (pinfunction "18_18") (pintype "bidirectional"))
    )
    (net (code "121") (name "unconnected-(CARD1-Pad19)") (class "Default")
      (node (ref "CARD1") (pin "19") (pinfunction "19_19") (pintype "bidirectional"))
    )
    (net (code "122") (name "unconnected-(CARD1-Pad20)") (class "Default")
      (node (ref "CARD1") (pin "20") (pinfunction "20_20") (pintype "bidirectional"))
    )
    (net (code "123") (name "unconnected-(CARD1-Pad21)") (class "Default")
      (node (ref "CARD1") (pin "21") (pinfunction "21_21") (pintype "bidirectional"))
    )
    (net (code "124") (name "unconnected-(CARD1-Pad22)") (class "Default")
      (node (ref "CARD1") (pin "22") (pinfunction "22_22") (pintype "bidirectional"))
    )
    (net (code "125") (name "unconnected-(CARD1-Pad23)") (class "Default")
      (node (ref "CARD1") (pin "23") (pinfunction "23_23") (pintype "bidirectional"))
    )
    (net (code "126") (name "unconnected-(CARD1-Pad24)") (class "Default")
      (node (ref "CARD1") (pin "24") (pinfunction "24_24") (pintype "bidirectional"))
    )
    (net (code "127") (name "unconnected-(CARD1-Pad25)") (class "Default")
      (node (ref "CARD1") (pin "25") (pinfunction "25_25") (pintype "bidirectional"))
    )
    (net (code "128") (name "unconnected-(CARD1-Pad26)") (class "Default")
      (node (ref "CARD1") (pin "26") (pinfunction "26_26") (pintype "bidirectional"))
    )
    (net (code "129") (name "unconnected-(CARD1-Pad35)") (class "Default")
      (node (ref "CARD1") (pin "35") (pinfunction "35_35") (pintype "bidirectional"))
    )
    (net (code "130") (name "unconnected-(CARD1-Pad36)") (class "Default")
      (node (ref "CARD1") (pin "36") (pinfunction "36_36") (pintype "bidirectional"))
    )
    (net (code "131") (name "unconnected-(CARD1-Pad37)") (class "Default")
      (node (ref "CARD1") (pin "37") (pinfunction "37_37") (pintype "bidirectional"))
    )
    (net (code "132") (name "unconnected-(CARD1-Pad38)") (class "Default")
      (node (ref "CARD1") (pin "38") (pinfunction "38_38") (pintype "bidirectional"))
    )
    (net (code "133") (name "unconnected-(CARD1-Pad39)") (class "Default")
      (node (ref "CARD1") (pin "39") (pinfunction "39_39") (pintype "bidirectional"))
    )
    (net (code "134") (name "unconnected-(CARD1-Pad40)") (class "Default")
      (node (ref "CARD1") (pin "40") (pinfunction "40_40") (pintype "bidirectional"))
    )
    (net (code "135") (name "unconnected-(CARD1-Pad41)") (class "Default")
      (node (ref "CARD1") (pin "41") (pinfunction "41_41") (pintype "bidirectional"))
    )
    (net (code "136") (name "unconnected-(CARD1-Pad42)") (class "Default")
      (node (ref "CARD1") (pin "42") (pinfunction "42_42") (pintype "bidirectional"))
    )
    (net (code "137") (name "unconnected-(CARD1-Pad43)") (class "Default")
      (node (ref "CARD1") (pin "43") (pinfunction "43_43") (pintype "bidirectional"))
    )
    (net (code "138") (name "unconnected-(CARD1-Pad44)") (class "Default")
      (node (ref "CARD1") (pin "44") (pinfunction "44_44") (pintype "bidirectional"))
    )
    (net (code "139") (name "unconnected-(CARD1-Pad45)") (class "Default")
      (node (ref "CARD1") (pin "45") (pinfunction "45_45") (pintype "bidirectional"))
    )
    (net (code "140") (name "unconnected-(CARD1-Pad46)") (class "Default")
      (node (ref "CARD1") (pin "46") (pinfunction "46_46") (pintype "bidirectional"))
    )
    (net (code "141") (name "unconnected-(CARD1-Pad47)") (class "Default")
      (node (ref "CARD1") (pin "47") (pinfunction "47_47") (pintype "bidirectional"))
    )
    (net (code "142") (name "unconnected-(CARD1-Pad48)") (class "Default")
      (node (ref "CARD1") (pin "48") (pinfunction "48_48") (pintype "bidirectional"))
    )
    (net (code "143") (name "unconnected-(CARD1-Pad49)") (class "Default")
      (node (ref "CARD1") (pin "49") (pinfunction "49_49") (pintype "bidirectional"))
    )
    (net (code "144") (name "unconnected-(CARD1-Pad50)") (class "Default")
      (node (ref "CARD1") (pin "50") (pinfunction "50_50") (pintype "bidirectional"))
    )
    (net (code "145") (name "unconnected-(CARD1-Pad51)") (class "Default")
      (node (ref "CARD1") (pin "51") (pinfunction "51_51") (pintype "bidirectional"))
    )
    (net (code "146") (name "unconnected-(CARD1-Pad52)") (class "Default")
      (node (ref "CARD1") (pin "52") (pinfunction "52_52") (pintype "bidirectional"))
    )
    (net (code "147") (name "unconnected-(CARD1-Pad53)") (class "Default")
      (node (ref "CARD1") (pin "53") (pinfunction "53_53") (pintype "bidirectional"))
    )
    (net (code "148") (name "unconnected-(CARD1-Pad54)") (class "Default")
      (node (ref "CARD1") (pin "54") (pinfunction "54_54") (pintype "bidirectional"))
    )
    (net (code "149") (name "unconnected-(CARD1-Pad55)") (class "Default")
      (node (ref "CARD1") (pin "55") (pinfunction "55_55") (pintype "bidirectional"))
    )
    (net (code "150") (name "unconnected-(CARD1-Pad56)") (class "Default")
      (node (ref "CARD1") (pin "56") (pinfunction "56_56") (pintype "bidirectional"))
    )
    (net (code "151") (name "unconnected-(CARD1-Pad57)") (class "Default")
      (node (ref "CARD1") (pin "57") (pinfunction "57_57") (pintype "bidirectional"))
    )
    (net (code "152") (name "unconnected-(CARD1-Pad58)") (class "Default")
      (node (ref "CARD1") (pin "58") (pinfunction "58_58") (pintype "bidirectional"))
    )
    (net (code "153") (name "unconnected-(CARD1-Pad59)") (class "Default")
      (node (ref "CARD1") (pin "59") (pinfunction "59_59") (pintype "bidirectional"))
    )
    (net (code "154") (name "unconnected-(CARD1-Pad60)") (class "Default")
      (node (ref "CARD1") (pin "60") (pinfunction "60_60") (pintype "bidirectional"))
    )
    (net (code "155") (name "unconnected-(CARD1-Pad61)") (class "Default")
      (node (ref "CARD1") (pin "61") (pinfunction "61_61") (pintype "bidirectional"))
    )
    (net (code "156") (name "unconnected-(CARD1-Pad62)") (class "Default")
      (node (ref "CARD1") (pin "62") (pinfunction "62_62") (pintype "bidirectional"))
    )
    (net (code "157") (name "unconnected-(U4-LINEIN-Pad48)") (class "Default")
      (node (ref "U4") (pin "48") (pinfunction "LINEIN_48") (pintype "bidirectional"))
    )
    (net (code "158") (name "unconnected-(U4-MICN-Pad2)") (class "Default")
      (node (ref "U4") (pin "2") (pinfunction "MICN_2") (pintype "bidirectional"))
    )
    (net (code "159") (name "unconnected-(U4-MICP-Pad1)") (class "Default")
      (node (ref "U4") (pin "1") (pinfunction "MICP_1") (pintype "bidirectional"))
    )
    (net (code "160") (name "unconnected-(U4-TX-Pad27)") (class "Default")
      (node (ref "U4") (pin "27") (pinfunction "TX_27") (pintype "bidirectional"))
    )
    (net (code "161") (name "unconnected-(U4-VCO-Pad15)") (class "Default")
      (node (ref "U4") (pin "15") (pinfunction "VCO_15") (pintype "bidirectional"))
    )
    (net (code "162") (name "unconnected-(U5-ADC6-Pad19)") (class "Default")
      (node (ref "U5") (pin "19") (pinfunction "ADC6_19") (pintype "bidirectional"))
    )
    (net (code "163") (name "unconnected-(U5-ADC7-Pad22)") (class "Default")
      (node (ref "U5") (pin "22") (pinfunction "ADC7_22") (pintype "bidirectional"))
    )
    (net (code "164") (name "unconnected-(U5-PB2(SS{slash}OC1B)-Pad14)") (class "Default")
      (node (ref "U5") (pin "14") (pinfunction "PB2(SS/OC1B)_14") (pintype "bidirectional"))
    )
    (net (code "165") (name "unconnected-(U5-PD3(INT1)-Pad1)") (class "Default")
      (node (ref "U5") (pin "1") (pinfunction "PD3(INT1)_1") (pintype "bidirectional"))
    )
    (net (code "166") (name "unconnected-(U5-PD4(XCK{slash}T0)-Pad2)") (class "Default")
      (node (ref "U5") (pin "2") (pinfunction "PD4(XCK/T0)_2") (pintype "bidirectional"))
    )
    (net (code "167") (name "unconnected-(U7-NC-Pad1)") (class "Default")
      (node (ref "U7") (pin "1") (pinfunction "NC_1") (pintype "bidirectional"))
    )
    (net (code "168") (name "unconnected-(U7-RSV-Pad8)") (class "Default")
      (node (ref "U7") (pin "8") (pinfunction "RSV_8") (pintype "bidirectional"))
    )
    (net (code "169") (name "unconnected-(U8-RA2-Pad21)") (class "Default")
      (node (ref "U8") (pin "21") (pinfunction "RA2_21") (pintype "bidirectional"))
    )
    (net (code "170") (name "unconnected-(U8-RA4-Pad23)") (class "Default")
      (node (ref "U8") (pin "23") (pinfunction "RA4_23") (pintype "bidirectional"))
    )
    (net (code "171") (name "unconnected-(U8-RA5-Pad24)") (class "Default")
      (node (ref "U8") (pin "24") (pinfunction "RA5_24") (pintype "bidirectional"))
    )
    (net (code "172") (name "unconnected-(U8-RA6-Pad31)") (class "Default")
      (node (ref "U8") (pin "31") (pinfunction "RA6_31") (pintype "bidirectional"))
    )
    (net (code "173") (name "unconnected-(U8-RA7-Pad30)") (class "Default")
      (node (ref "U8") (pin "30") (pinfunction "RA7_30") (pintype "bidirectional"))
    )
    (net (code "174") (name "unconnected-(U8-RB0-Pad8)") (class "Default")
      (node (ref "U8") (pin "8") (pinfunction "RB0_8") (pintype "bidirectional"))
    )
    (net (code "175") (name "unconnected-(U8-RB5-Pad15)") (class "Default")
      (node (ref "U8") (pin "15") (pinfunction "RB5_15") (pintype "bidirectional"))
    )
    (net (code "176") (name "unconnected-(U8-RC0-Pad32)") (class "Default")
      (node (ref "U8") (pin "32") (pinfunction "RC0_32") (pintype "bidirectional"))
    )
    (net (code "177") (name "unconnected-(U8-RC1-Pad35)") (class "Default")
      (node (ref "U8") (pin "35") (pinfunction "RC1_35") (pintype "bidirectional"))
    )
    (net (code "178") (name "unconnected-(U8-RC4-Pad42)") (class "Default")
      (node (ref "U8") (pin "42") (pinfunction "RC4_42") (pintype "bidirectional"))
    )
    (net (code "179") (name "unconnected-(U8-RD0-Pad38)") (class "Default")
      (node (ref "U8") (pin "38") (pinfunction "RD0_38") (pintype "bidirectional"))
    )
    (net (code "180") (name "unconnected-(U8-RD4-Pad2)") (class "Default")
      (node (ref "U8") (pin "2") (pinfunction "RD4_2") (pintype "bidirectional"))
    )
    (net (code "181") (name "unconnected-(U8-RE0-Pad25)") (class "Default")
      (node (ref "U8") (pin "25") (pinfunction "RE0_25") (pintype "bidirectional"))
    )
    (net (code "182") (name "unconnected-(U8-RE1-Pad26)") (class "Default")
      (node (ref "U8") (pin "26") (pinfunction "RE1_26") (pintype "bidirectional"))
    )
    (net (code "183") (name "unconnected-(U8-RE2-Pad27)") (class "Default")
      (node (ref "U8") (pin "27") (pinfunction "RE2_27") (pintype "bidirectional"))
    )
    (net (code "184") (name "unconnected-(U10-BP-Pad4)") (class "Default")
      (node (ref "U10") (pin "4") (pinfunction "BP_4") (pintype "input"))
    )
  )
)
